# MK66MCU.net
KiCad netlist of a schematic drawn in Altium Designer
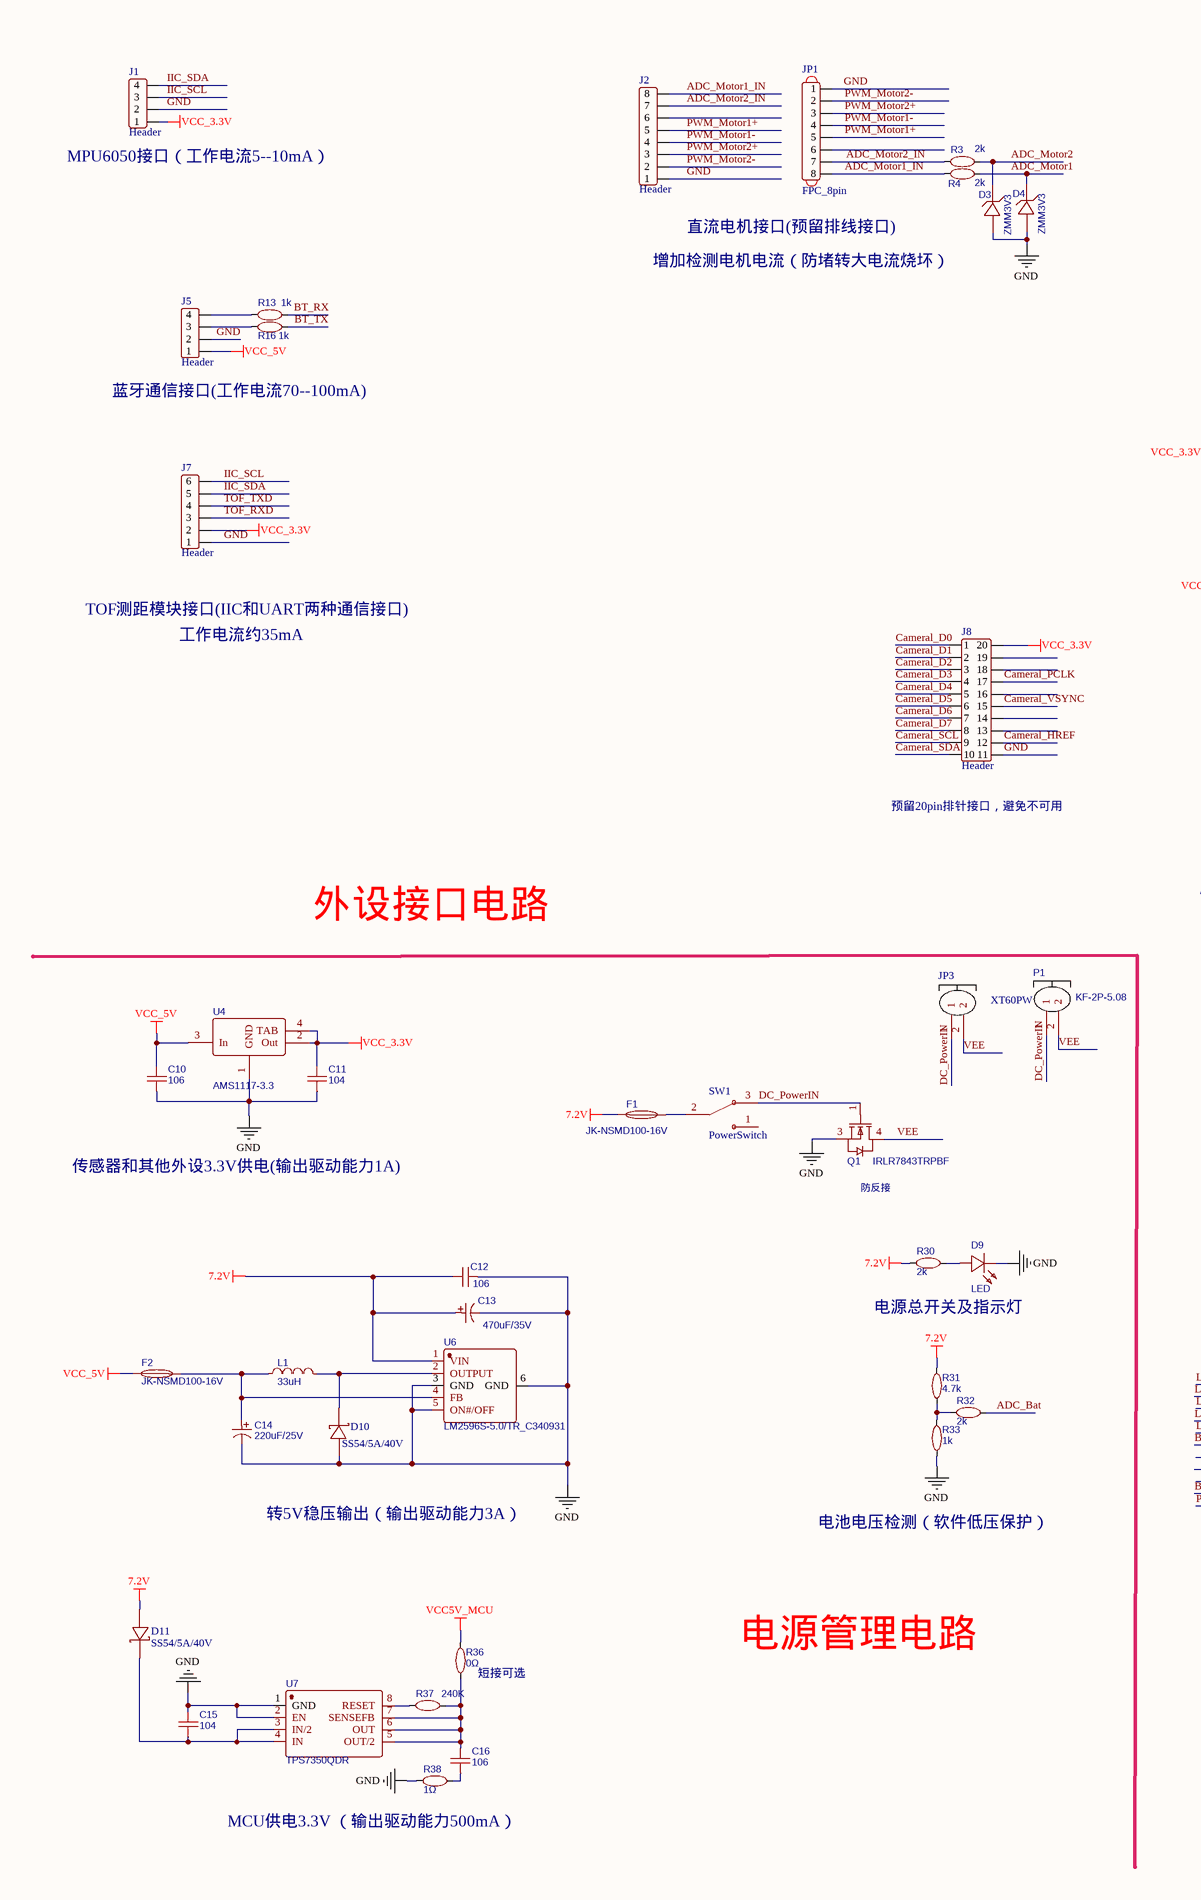
[diagram p0: MK66MCU.SchDoc, left]
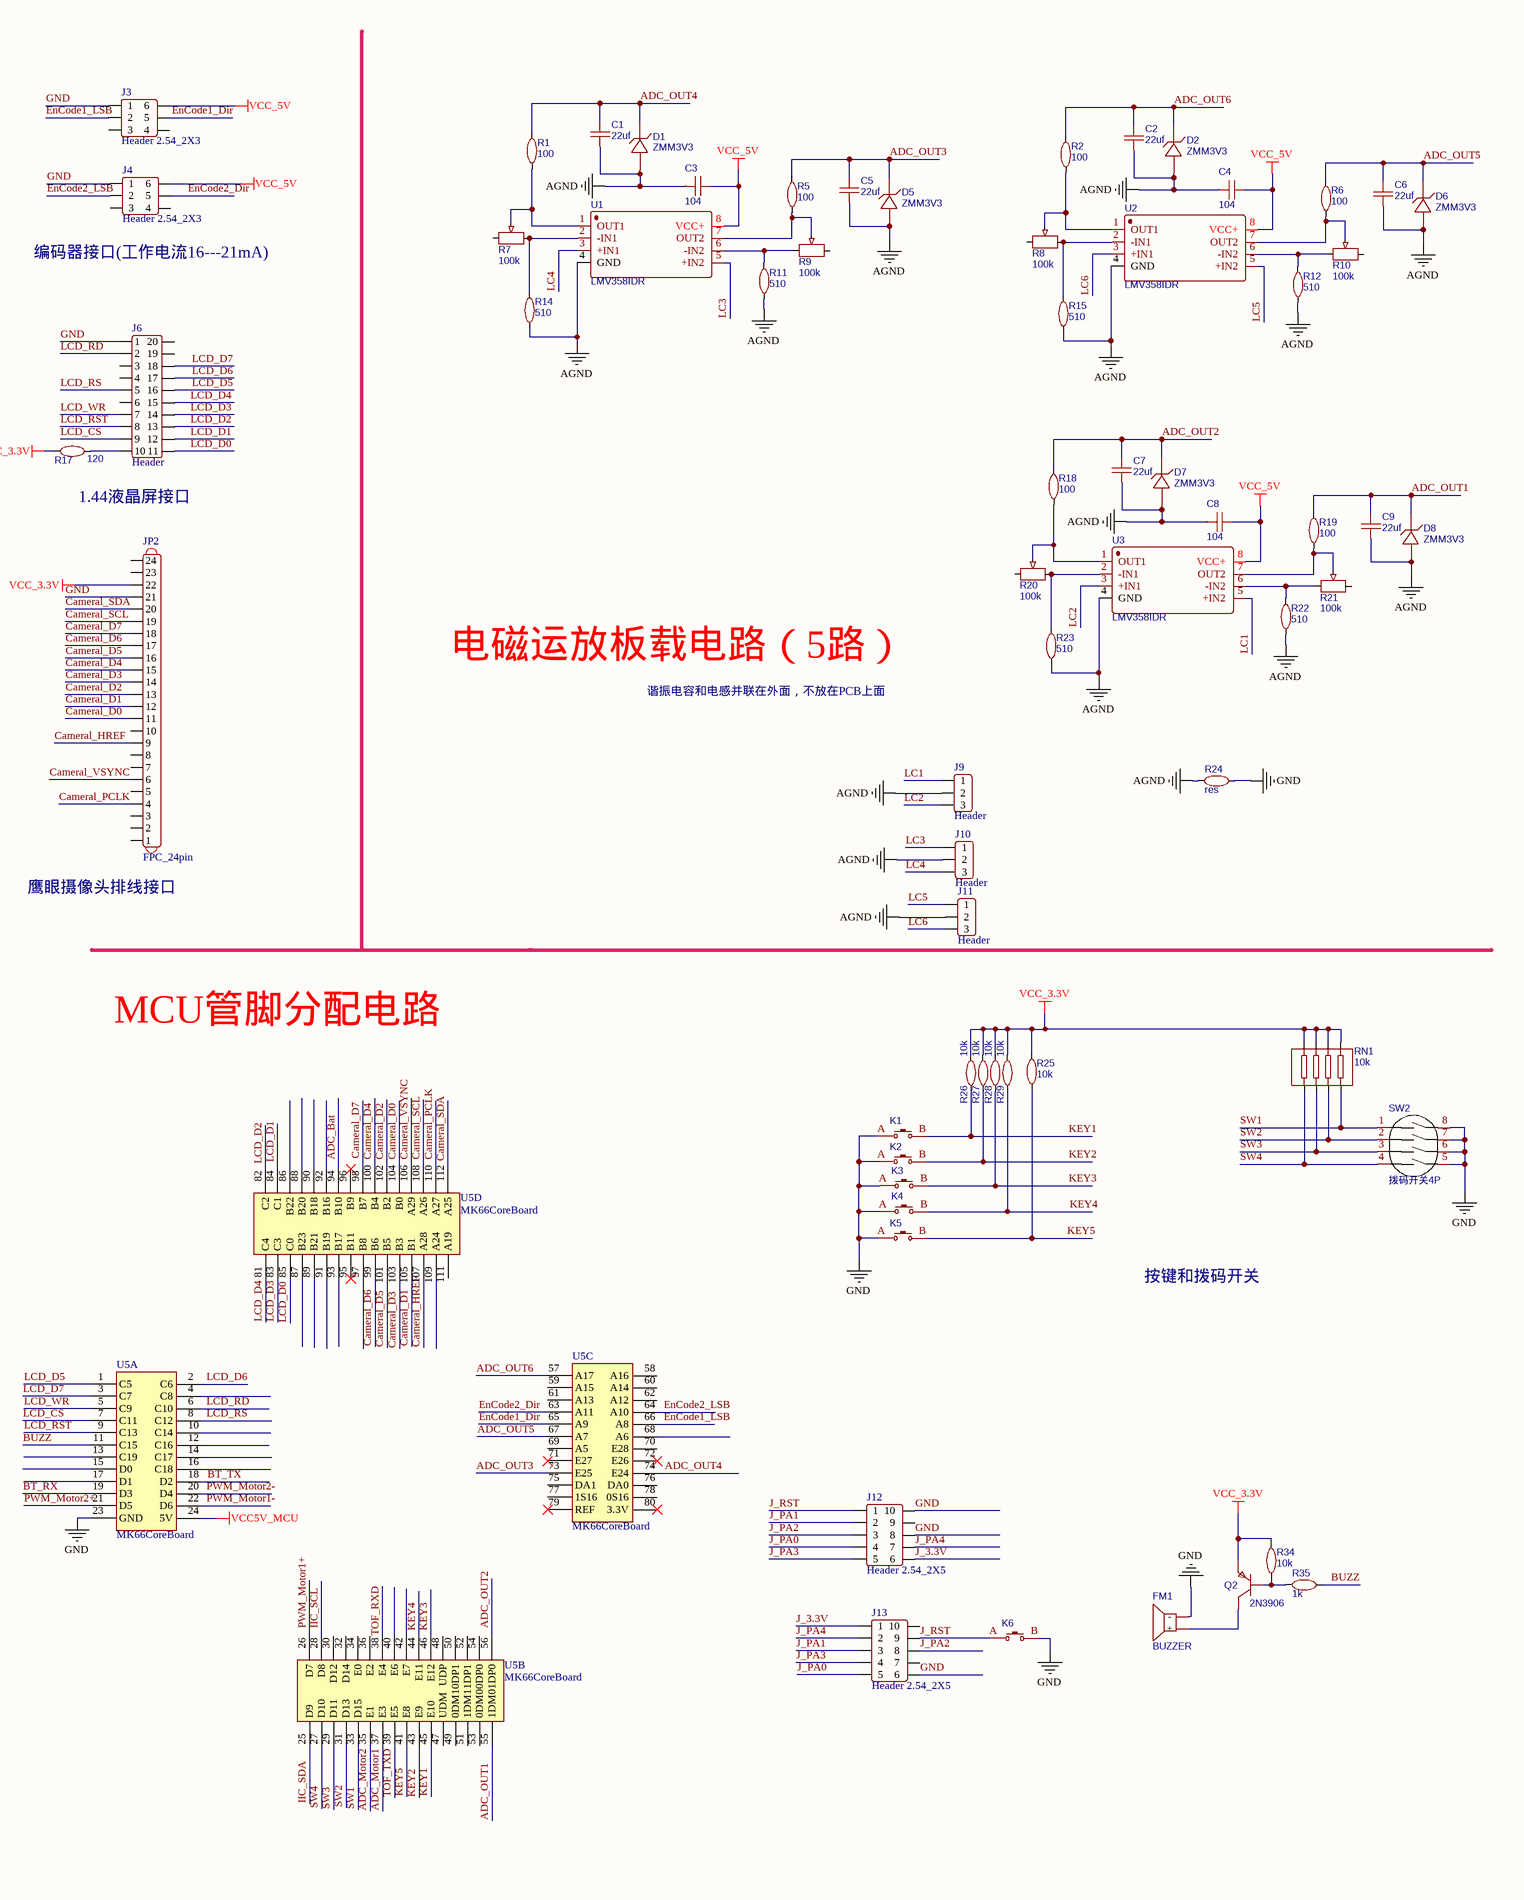
[diagram p1: MK66MCU.SchDoc, right]

(export (version "E")
  (design (tool "Eeschema 10.0.6"))
  (components
    (comp (ref "C1")
      (value "22uf")
      (footprint "CAP_0603")
      (fields
        (field (name "BOM_SUPPLIER PART") "C307348")
        (field (name "BOM_MANUFACTURER PART") "CL10B104KB8WPNC")
        (field (name "CONTRIBUTOR") "LCSC")
      )
      (libsource (lib "LTC_Library1") (part "CAP_0603"))
    )
    (comp (ref "C2")
      (value "22uf")
      (footprint "CAP_0603")
      (fields
        (field (name "BOM_SUPPLIER PART") "C307348")
        (field (name "BOM_MANUFACTURER PART") "CL10B104KB8WPNC")
        (field (name "CONTRIBUTOR") "LCSC")
      )
      (libsource (lib "LTC_Library1") (part "CAP_0603"))
    )
    (comp (ref "C3")
      (value "104")
      (footprint "CAP_0603")
      (fields
        (field (name "BOM_SUPPLIER PART") "C307348")
        (field (name "BOM_MANUFACTURER PART") "CL10B104KB8WPNC")
        (field (name "CONTRIBUTOR") "LCSC")
      )
      (libsource (lib "LTC_Library1") (part "CAP_0603"))
    )
    (comp (ref "C4")
      (value "104")
      (footprint "CAP_0603")
      (fields
        (field (name "BOM_SUPPLIER PART") "C307348")
        (field (name "BOM_MANUFACTURER PART") "CL10B104KB8WPNC")
        (field (name "CONTRIBUTOR") "LCSC")
      )
      (libsource (lib "LTC_Library1") (part "CAP_0603"))
    )
    (comp (ref "C5")
      (value "22uf")
      (footprint "CAP_0603")
      (fields
        (field (name "BOM_SUPPLIER PART") "C307348")
        (field (name "BOM_MANUFACTURER PART") "CL10B104KB8WPNC")
        (field (name "CONTRIBUTOR") "LCSC")
      )
      (libsource (lib "LTC_Library1") (part "CAP_0603"))
    )
    (comp (ref "C6")
      (value "22uf")
      (footprint "CAP_0603")
      (fields
        (field (name "BOM_SUPPLIER PART") "C307348")
        (field (name "BOM_MANUFACTURER PART") "CL10B104KB8WPNC")
        (field (name "CONTRIBUTOR") "LCSC")
      )
      (libsource (lib "LTC_Library1") (part "CAP_0603"))
    )
    (comp (ref "C7")
      (value "22uf")
      (footprint "CAP_0603")
      (fields
        (field (name "BOM_SUPPLIER PART") "C307348")
        (field (name "BOM_MANUFACTURER PART") "CL10B104KB8WPNC")
        (field (name "CONTRIBUTOR") "LCSC")
      )
      (libsource (lib "LTC_Library1") (part "CAP_0603"))
    )
    (comp (ref "C8")
      (value "104")
      (footprint "CAP_0603")
      (fields
        (field (name "BOM_SUPPLIER PART") "C307348")
        (field (name "BOM_MANUFACTURER PART") "CL10B104KB8WPNC")
        (field (name "CONTRIBUTOR") "LCSC")
      )
      (libsource (lib "LTC_Library1") (part "CAP_0603"))
    )
    (comp (ref "C9")
      (value "22uf")
      (footprint "CAP_0603")
      (fields
        (field (name "BOM_SUPPLIER PART") "C307348")
        (field (name "BOM_MANUFACTURER PART") "CL10B104KB8WPNC")
        (field (name "CONTRIBUTOR") "LCSC")
      )
      (libsource (lib "LTC_Library1") (part "CAP_0603"))
    )
    (comp (ref "C10")
      (value "106")
      (footprint "CAP_0603")
      (fields
        (field (name "BOM_SUPPLIER PART") "C307348")
        (field (name "BOM_MANUFACTURER PART") "CL10B104KB8WPNC")
        (field (name "CONTRIBUTOR") "LCSC")
      )
      (libsource (lib "LTC_Library1") (part "CAP_0603"))
    )
    (comp (ref "C11")
      (value "104")
      (footprint "CAP_0603")
      (fields
        (field (name "BOM_SUPPLIER PART") "C307348")
        (field (name "BOM_MANUFACTURER PART") "CL10B104KB8WPNC")
        (field (name "CONTRIBUTOR") "LCSC")
      )
      (libsource (lib "LTC_Library1") (part "CAP_0603"))
    )
    (comp (ref "C12")
      (value "106")
      (footprint "CAP_0603")
      (fields
        (field (name "BOM_SUPPLIER PART") "C307348")
        (field (name "BOM_MANUFACTURER PART") "CL10B104KB8WPNC")
        (field (name "CONTRIBUTOR") "LCSC")
      )
      (libsource (lib "LTC_Library1") (part "CAP_0603"))
    )
    (comp (ref "C13")
      (value "470uF/35V")
      (footprint "CAPE_SMD_F_8.4")
      (description "贴片电解电容")
      (fields
        (field (name "BOM_MANUFACTURER PART") "RVT1C221M0607")
        (field (name "BOM_SUPPLIER PART") "C72496")
      )
      (libsource (lib "LTC_Library1") (part "CAP_E_SMD"))
    )
    (comp (ref "C14")
      (value "220uF/25V")
      (footprint "CAPE_SMD_D_6.4")
      (description "贴片电解电容")
      (fields
        (field (name "BOM_MANUFACTURER PART") "RVT1C221M0607")
        (field (name "BOM_SUPPLIER PART") "C72496")
      )
      (libsource (lib "") (part "CAP_E_SMD_1"))
    )
    (comp (ref "C15")
      (value "104")
      (footprint "CAP_0603")
      (fields
        (field (name "BOM_SUPPLIER PART") "C307348")
        (field (name "BOM_MANUFACTURER PART") "CL10B104KB8WPNC")
        (field (name "CONTRIBUTOR") "LCSC")
      )
      (libsource (lib "LTC_Library1") (part "CAP_0603"))
    )
    (comp (ref "C16")
      (value "106")
      (footprint "CAP_0603")
      (fields
        (field (name "BOM_SUPPLIER PART") "C307348")
        (field (name "BOM_MANUFACTURER PART") "CL10B104KB8WPNC")
        (field (name "CONTRIBUTOR") "LCSC")
      )
      (libsource (lib "LTC_Library1") (part "CAP_0603"))
    )
    (comp (ref "D1")
      (value "ZMM3V3")
      (footprint "LL-34_L3.5-W1.5-RD")
      (fields (field (name "BOM_SUPPLIER PART") "C8056"))
      (libsource (lib "SmartCar_Library") (part "ZMM3V3"))
    )
    (comp (ref "D2")
      (value "ZMM3V3")
      (footprint "LL-34_L3.5-W1.5-RD")
      (fields (field (name "BOM_SUPPLIER PART") "C8056"))
      (libsource (lib "SmartCar_Library") (part "ZMM3V3"))
    )
    (comp (ref "D3")
      (value "ZMM3V3")
      (footprint "LL-34_L3.5-W1.5-RD")
      (fields (field (name "BOM_SUPPLIER PART") "C8056"))
      (libsource (lib "SmartCar_Library") (part "ZMM3V3"))
    )
    (comp (ref "D4")
      (value "ZMM3V3")
      (footprint "LL-34_L3.5-W1.5-RD")
      (fields (field (name "BOM_SUPPLIER PART") "C8056"))
      (libsource (lib "SmartCar_Library") (part "ZMM3V3"))
    )
    (comp (ref "D5")
      (value "ZMM3V3")
      (footprint "LL-34_L3.5-W1.5-RD")
      (fields (field (name "BOM_SUPPLIER PART") "C8056"))
      (libsource (lib "SmartCar_Library") (part "ZMM3V3"))
    )
    (comp (ref "D6")
      (value "ZMM3V3")
      (footprint "LL-34_L3.5-W1.5-RD")
      (fields (field (name "BOM_SUPPLIER PART") "C8056"))
      (libsource (lib "SmartCar_Library") (part "ZMM3V3"))
    )
    (comp (ref "D7")
      (value "ZMM3V3")
      (footprint "LL-34_L3.5-W1.5-RD")
      (fields (field (name "BOM_SUPPLIER PART") "C8056"))
      (libsource (lib "SmartCar_Library") (part "ZMM3V3"))
    )
    (comp (ref "D8")
      (value "ZMM3V3")
      (footprint "LL-34_L3.5-W1.5-RD")
      (fields (field (name "BOM_SUPPLIER PART") "C8056"))
      (libsource (lib "SmartCar_Library") (part "ZMM3V3"))
    )
    (comp (ref "D9")
      (value "LED")
      (footprint "LED_0603_B")
      (description "发光LED")
      (fields
        (field (name "BOM_MANUFACTURER PART") "D-G080508G1")
        (field (name "BOM_SUPPLIER PART") "C107402")
        (field (name "CONTRIBUTOR") "LCSC")
      )
      (libsource (lib "LTC_Library1") (part "LED_0603"))
    )
    (comp (ref "D10")
      (value "SS54/5A/40V")
      (footprint "DO214_SMA")
      (libsource (lib "LTC_Library1") (part "SS54"))
    )
    (comp (ref "D11")
      (value "SS54/5A/40V")
      (footprint "DO214_SMA")
      (libsource (lib "LTC_Library1") (part "SS54"))
    )
    (comp (ref "F1")
      (value "JK-NSMD100-16V")
      (footprint "FUSE_1210")
      (fields (field (name "BOM_SUPPLIER PART") "C369161") (field (name "CONTRIBUTOR") "LCSC"))
      (libsource (lib "SmartCar_Library") (part "JK-NSMD100-16V"))
    )
    (comp (ref "F2")
      (value "JK-NSMD100-16V")
      (footprint "F1206")
      (fields (field (name "BOM_SUPPLIER PART") "C369161") (field (name "CONTRIBUTOR") "LCSC"))
      (libsource (lib "SmartCar_Library") (part "JK-NSMD100-16V"))
    )
    (comp (ref "FM1")
      (value "BUZZER")
      (footprint "BUZZ-12*7.5")
      (description "蜂鸣器")
      (fields (field (name "BOM_MANUFACTURER PART") "TMB12A12") (field (name "BOM_SUPPLIER PART") "C96079"))
      (libsource (lib "LTC_Library1") (part "BUZZER"))
    )
    (comp (ref "J1")
      (value "Header")
      (footprint "Header 2.54X4")
      (libsource (lib "LTC_Library1") (part "Header 2.54_4"))
    )
    (comp (ref "J2")
      (value "Header")
      (footprint "Header 2.54X8")
      (libsource (lib "LTC_Library1") (part "Header 2.54_8"))
    )
    (comp (ref "J3")
      (value "Header 2.54_2X3")
      (footprint "IDC_6P")
      (libsource (lib "LTC_Library1") (part "Header 2.54_2X3"))
    )
    (comp (ref "J4")
      (value "Header 2.54_2X3")
      (footprint "IDC_6P")
      (libsource (lib "LTC_Library1") (part "Header 2.54_2X3"))
    )
    (comp (ref "J5")
      (value "Header")
      (footprint "Header F 2.54X4")
      (libsource (lib "LTC_Library1") (part "Header 2.54_4"))
    )
    (comp (ref "J6")
      (value "Header")
      (footprint "Header F 2.54_2x10")
      (libsource (lib "LTC_Library1") (part "Header 2.54_2X10"))
    )
    (comp (ref "J7")
      (value "Header")
      (footprint "Header 2.54X6")
      (libsource (lib "LTC_Library1") (part "Header 2.54_6"))
    )
    (comp (ref "J8")
      (value "Header")
      (footprint "Header F 2.54_2x10")
      (libsource (lib "LTC_Library1") (part "Header 2.54_2X10"))
    )
    (comp (ref "J9")
      (value "Header")
      (footprint "Header 2.54X3")
      (libsource (lib "LTC_Library1") (part "Header 2.54_3"))
    )
    (comp (ref "J10")
      (value "Header")
      (footprint "Header 2.54X3")
      (libsource (lib "LTC_Library1") (part "Header 2.54_3"))
    )
    (comp (ref "J11")
      (value "Header")
      (footprint "Header 2.54X3")
      (libsource (lib "LTC_Library1") (part "Header 2.54_3"))
    )
    (comp (ref "J12")
      (value "Header 2.54_2X5")
      (footprint "Header 2.54_2X5")
      (libsource (lib "LTC_Library1") (part "Header 2.54_2X5"))
    )
    (comp (ref "J13")
      (value "Header 2.54_2X5")
      (footprint "IDC_10P")
      (libsource (lib "LTC_Library1") (part "Header 2.54_2X5"))
    )
    (comp (ref "JP1")
      (value "FPC_8pin")
      (footprint "FPC_1.0_8P")
      (libsource (lib "LTC_Library1") (part "FPC_8pin"))
    )
    (comp (ref "JP2")
      (value "FPC_24pin")
      (footprint "FPC_0.5_24P")
      (libsource (lib "External Interface") (part "FPC_24pin"))
    )
    (comp (ref "JP3")
      (value "XT60PW")
      (footprint "XT60PW")
      (libsource (lib "SmartCar_Library") (part "XT60PW"))
    )
    (comp (ref "K1")
      (value "TS-Button_2P")
      (footprint "SW_SMD_6.1*3.7")
      (description "贴片按键 3*6*2.5")
      (fields
        (field (name "BOM_SUPPLIER PART") "C455236")
        (field (name "BOM_MANUFACTURER PART") "TS-1007S-26")
        (field (name "CONTRIBUTOR") "LCSC")
      )
      (libsource (lib "LTC_Library1") (part "TS-Button_2P"))
    )
    (comp (ref "K2")
      (value "TS-Button_2P")
      (footprint "SW_SMD_6.1*3.7")
      (description "贴片按键 3*6*2.5")
      (fields
        (field (name "BOM_SUPPLIER PART") "C455236")
        (field (name "BOM_MANUFACTURER PART") "TS-1007S-26")
        (field (name "CONTRIBUTOR") "LCSC")
      )
      (libsource (lib "LTC_Library1") (part "TS-Button_2P"))
    )
    (comp (ref "K3")
      (value "TS-Button_2P")
      (footprint "SW_SMD_6.1*3.7")
      (description "贴片按键 3*6*2.5")
      (fields
        (field (name "BOM_SUPPLIER PART") "C455236")
        (field (name "BOM_MANUFACTURER PART") "TS-1007S-26")
        (field (name "CONTRIBUTOR") "LCSC")
      )
      (libsource (lib "LTC_Library1") (part "TS-Button_2P"))
    )
    (comp (ref "K4")
      (value "TS-Button_2P")
      (footprint "SW_SMD_6.1*3.7")
      (description "贴片按键 3*6*2.5")
      (fields
        (field (name "BOM_SUPPLIER PART") "C455236")
        (field (name "BOM_MANUFACTURER PART") "TS-1007S-26")
        (field (name "CONTRIBUTOR") "LCSC")
      )
      (libsource (lib "LTC_Library1") (part "TS-Button_2P"))
    )
    (comp (ref "K5")
      (value "TS-Button_2P")
      (footprint "SW_SMD_6.1*3.7")
      (description "贴片按键 3*6*2.5")
      (fields
        (field (name "BOM_SUPPLIER PART") "C455236")
        (field (name "BOM_MANUFACTURER PART") "TS-1007S-26")
        (field (name "CONTRIBUTOR") "LCSC")
      )
      (libsource (lib "LTC_Library1") (part "TS-Button_2P"))
    )
    (comp (ref "K6")
      (value "TS-Button_2P")
      (footprint "SW_SMD_6.1*3.7")
      (description "贴片按键 3*6*2.5")
      (fields
        (field (name "BOM_SUPPLIER PART") "C455236")
        (field (name "BOM_MANUFACTURER PART") "TS-1007S-26")
        (field (name "CONTRIBUTOR") "LCSC")
      )
      (libsource (lib "LTC_Library1") (part "TS-Button_2P"))
    )
    (comp (ref "L1")
      (value "33uH")
      (footprint "IND-SMD_L8.0-W8.0")
      (fields
        (field (name "BOM_SUPPLIER PART") "C295130")
        (field (name "BOM_MANUFACTURER PART") "NLV25T-330J-EF")
        (field (name "CONTRIBUTOR") "LCSC")
      )
      (libsource (lib "SmartCar_Library") (part "Inductor"))
    )
    (comp (ref "P1")
      (value "KF-2P-5.08")
      (footprint "KF_2P-5.08")
      (description "端子2P")
      (fields
        (field (name "BOM_MANUFACTURER PART") "WJ500H-5.08-2P")
        (field (name "BOM_SUPPLIER PART") "C8478")
      )
      (libsource (lib "LTC_Library1") (part "KF-2P-5.08"))
    )
    (comp (ref "Q1")
      (value "IRLR7843TRPBF")
      (footprint "TO-252-2")
      (description "MOS管")
      (fields (field (name "BOM_SUPPLIER PART") "C21988"))
      (libsource (lib "LTC_Library1") (part "IRLR7843TRPBF"))
    )
    (comp (ref "Q2")
      (value "2N3906")
      (footprint "TO_92A")
      (description "三极管PNP")
      (fields (field (name "BOM_SUPPLIER PART") "C305396") (field (name "CONTRIBUTOR") "LCSC"))
      (libsource (lib "LTC_Library1") (part "2N3906"))
    )
    (comp (ref "R1")
      (value "100")
      (footprint "RES_0603")
      (fields
        (field (name "BOM_MANUFACTURER PART") "RC0402JR-07100KL")
        (field (name "BOM_SUPPLIER PART") "C106234")
      )
      (libsource (lib "LTC_Library1") (part "RES_0603"))
    )
    (comp (ref "R2")
      (value "100")
      (footprint "RES_0603")
      (fields
        (field (name "BOM_MANUFACTURER PART") "RC0402JR-07100KL")
        (field (name "BOM_SUPPLIER PART") "C106234")
      )
      (libsource (lib "LTC_Library1") (part "RES_0603"))
    )
    (comp (ref "R3")
      (value "2k")
      (footprint "RES_0603")
      (fields
        (field (name "BOM_MANUFACTURER PART") "RC0402JR-07100KL")
        (field (name "BOM_SUPPLIER PART") "C106234")
      )
      (libsource (lib "LTC_Library1") (part "RES_0603"))
    )
    (comp (ref "R4")
      (value "2k")
      (footprint "RES_0603")
      (fields
        (field (name "BOM_MANUFACTURER PART") "RC0402JR-07100KL")
        (field (name "BOM_SUPPLIER PART") "C106234")
      )
      (libsource (lib "LTC_Library1") (part "RES_0603"))
    )
    (comp (ref "R5")
      (value "100")
      (footprint "RES_0603")
      (fields
        (field (name "BOM_MANUFACTURER PART") "RC0402JR-07100KL")
        (field (name "BOM_SUPPLIER PART") "C106234")
      )
      (libsource (lib "LTC_Library1") (part "RES_0603"))
    )
    (comp (ref "R6")
      (value "100")
      (footprint "RES_0603")
      (fields
        (field (name "BOM_MANUFACTURER PART") "RC0402JR-07100KL")
        (field (name "BOM_SUPPLIER PART") "C106234")
      )
      (libsource (lib "LTC_Library1") (part "RES_0603"))
    )
    (comp (ref "R7")
      (value "100k")
      (footprint "RES_POT-3296W")
      (description "可调电阻3296W")
      (fields
        (field (name "BOM_SUPPLIER PART") "C118963")
        (field (name "BOM_MANUFACTURER PART") "3296W-1-104")
        (field (name "CONTRIBUTOR") "LCSC")
      )
      (libsource (lib "LTC_Library1") (part "RES_POT-3296W"))
    )
    (comp (ref "R8")
      (value "100k")
      (footprint "RES_POT-3296W")
      (description "可调电阻3296W")
      (fields
        (field (name "BOM_SUPPLIER PART") "C118963")
        (field (name "BOM_MANUFACTURER PART") "3296W-1-104")
        (field (name "CONTRIBUTOR") "LCSC")
      )
      (libsource (lib "LTC_Library1") (part "RES_POT-3296W"))
    )
    (comp (ref "R9")
      (value "100k")
      (footprint "RES_POT-3296W")
      (description "可调电阻3296W")
      (fields
        (field (name "BOM_SUPPLIER PART") "C118963")
        (field (name "BOM_MANUFACTURER PART") "3296W-1-104")
        (field (name "CONTRIBUTOR") "LCSC")
      )
      (libsource (lib "LTC_Library1") (part "RES_POT-3296W"))
    )
    (comp (ref "R10")
      (value "100k")
      (footprint "RES_POT-3296W")
      (description "可调电阻3296W")
      (fields
        (field (name "BOM_SUPPLIER PART") "C118963")
        (field (name "BOM_MANUFACTURER PART") "3296W-1-104")
        (field (name "CONTRIBUTOR") "LCSC")
      )
      (libsource (lib "LTC_Library1") (part "RES_POT-3296W"))
    )
    (comp (ref "R11")
      (value "510")
      (footprint "RES_0603")
      (fields
        (field (name "BOM_MANUFACTURER PART") "RC0402JR-07100KL")
        (field (name "BOM_SUPPLIER PART") "C106234")
      )
      (libsource (lib "LTC_Library1") (part "RES_0603"))
    )
    (comp (ref "R12")
      (value "510")
      (footprint "RES_0603")
      (fields
        (field (name "BOM_MANUFACTURER PART") "RC0402JR-07100KL")
        (field (name "BOM_SUPPLIER PART") "C106234")
      )
      (libsource (lib "LTC_Library1") (part "RES_0603"))
    )
    (comp (ref "R13")
      (value "1k")
      (footprint "RES_0603")
      (fields
        (field (name "BOM_MANUFACTURER PART") "RC0402JR-07100KL")
        (field (name "BOM_SUPPLIER PART") "C106234")
      )
      (libsource (lib "LTC_Library1") (part "RES_0603"))
    )
    (comp (ref "R14")
      (value "510")
      (footprint "RES_0603")
      (fields
        (field (name "BOM_MANUFACTURER PART") "RC0402JR-07100KL")
        (field (name "BOM_SUPPLIER PART") "C106234")
      )
      (libsource (lib "LTC_Library1") (part "RES_0603"))
    )
    (comp (ref "R15")
      (value "510")
      (footprint "RES_0603")
      (fields
        (field (name "BOM_MANUFACTURER PART") "RC0402JR-07100KL")
        (field (name "BOM_SUPPLIER PART") "C106234")
      )
      (libsource (lib "LTC_Library1") (part "RES_0603"))
    )
    (comp (ref "R16")
      (value "1k")
      (footprint "RES_0603")
      (fields
        (field (name "BOM_MANUFACTURER PART") "RC0402JR-07100KL")
        (field (name "BOM_SUPPLIER PART") "C106234")
      )
      (libsource (lib "LTC_Library1") (part "RES_0603"))
    )
    (comp (ref "R17")
      (value "120")
      (footprint "RES_0603")
      (fields
        (field (name "BOM_MANUFACTURER PART") "RC0402JR-07100KL")
        (field (name "BOM_SUPPLIER PART") "C106234")
      )
      (libsource (lib "LTC_Library1") (part "RES_0603"))
    )
    (comp (ref "R18")
      (value "100")
      (footprint "RES_0603")
      (fields
        (field (name "BOM_MANUFACTURER PART") "RC0402JR-07100KL")
        (field (name "BOM_SUPPLIER PART") "C106234")
      )
      (libsource (lib "LTC_Library1") (part "RES_0603"))
    )
    (comp (ref "R19")
      (value "100")
      (footprint "RES_0603")
      (fields
        (field (name "BOM_MANUFACTURER PART") "RC0402JR-07100KL")
        (field (name "BOM_SUPPLIER PART") "C106234")
      )
      (libsource (lib "LTC_Library1") (part "RES_0603"))
    )
    (comp (ref "R20")
      (value "100k")
      (footprint "RES_POT-3296W")
      (description "可调电阻3296W")
      (fields
        (field (name "BOM_SUPPLIER PART") "C118963")
        (field (name "BOM_MANUFACTURER PART") "3296W-1-104")
        (field (name "CONTRIBUTOR") "LCSC")
      )
      (libsource (lib "LTC_Library1") (part "RES_POT-3296W"))
    )
    (comp (ref "R21")
      (value "100k")
      (footprint "RES_POT-3296W")
      (description "可调电阻3296W")
      (fields
        (field (name "BOM_SUPPLIER PART") "C118963")
        (field (name "BOM_MANUFACTURER PART") "3296W-1-104")
        (field (name "CONTRIBUTOR") "LCSC")
      )
      (libsource (lib "LTC_Library1") (part "RES_POT-3296W"))
    )
    (comp (ref "R22")
      (value "510")
      (footprint "RES_0603")
      (fields
        (field (name "BOM_MANUFACTURER PART") "RC0402JR-07100KL")
        (field (name "BOM_SUPPLIER PART") "C106234")
      )
      (libsource (lib "LTC_Library1") (part "RES_0603"))
    )
    (comp (ref "R23")
      (value "510")
      (footprint "RES_0603")
      (fields
        (field (name "BOM_MANUFACTURER PART") "RC0402JR-07100KL")
        (field (name "BOM_SUPPLIER PART") "C106234")
      )
      (libsource (lib "LTC_Library1") (part "RES_0603"))
    )
    (comp (ref "R24")
      (value "res")
      (footprint "RES_0805")
      (fields
        (field (name "BOM_MANUFACTURER PART") "RC0402JR-07100KL")
        (field (name "BOM_SUPPLIER PART") "C106234")
      )
      (libsource (lib "LTC_Library1") (part "RES_0805"))
    )
    (comp (ref "R25")
      (value "10k")
      (footprint "RES_0603")
      (fields
        (field (name "BOM_MANUFACTURER PART") "RC0402JR-07100KL")
        (field (name "BOM_SUPPLIER PART") "C106234")
      )
      (libsource (lib "LTC_Library1") (part "RES_0603"))
    )
    (comp (ref "R26")
      (value "10k")
      (footprint "RES_0603")
      (fields
        (field (name "BOM_MANUFACTURER PART") "RC0402JR-07100KL")
        (field (name "BOM_SUPPLIER PART") "C106234")
      )
      (libsource (lib "LTC_Library1") (part "RES_0603"))
    )
    (comp (ref "R27")
      (value "10k")
      (footprint "RES_0603")
      (fields
        (field (name "BOM_MANUFACTURER PART") "RC0402JR-07100KL")
        (field (name "BOM_SUPPLIER PART") "C106234")
      )
      (libsource (lib "LTC_Library1") (part "RES_0603"))
    )
    (comp (ref "R28")
      (value "10k")
      (footprint "RES_0603")
      (fields
        (field (name "BOM_MANUFACTURER PART") "RC0402JR-07100KL")
        (field (name "BOM_SUPPLIER PART") "C106234")
      )
      (libsource (lib "LTC_Library1") (part "RES_0603"))
    )
    (comp (ref "R29")
      (value "10k")
      (footprint "RES_0603")
      (fields
        (field (name "BOM_MANUFACTURER PART") "RC0402JR-07100KL")
        (field (name "BOM_SUPPLIER PART") "C106234")
      )
      (libsource (lib "LTC_Library1") (part "RES_0603"))
    )
    (comp (ref "R30")
      (value "2k")
      (footprint "RES_0603")
      (fields
        (field (name "BOM_MANUFACTURER PART") "RC0402JR-07100KL")
        (field (name "BOM_SUPPLIER PART") "C106234")
      )
      (libsource (lib "LTC_Library1") (part "RES_0603"))
    )
    (comp (ref "R31")
      (value "4.7k")
      (footprint "RES_0603")
      (fields
        (field (name "BOM_MANUFACTURER PART") "RC0402JR-07100KL")
        (field (name "BOM_SUPPLIER PART") "C106234")
      )
      (libsource (lib "LTC_Library1") (part "RES_0603"))
    )
    (comp (ref "R32")
      (value "2k")
      (footprint "RES_0603")
      (fields
        (field (name "BOM_MANUFACTURER PART") "RC0402JR-07100KL")
        (field (name "BOM_SUPPLIER PART") "C106234")
      )
      (libsource (lib "LTC_Library1") (part "RES_0603"))
    )
    (comp (ref "R33")
      (value "1k")
      (footprint "RES_0603")
      (fields
        (field (name "BOM_MANUFACTURER PART") "RC0402JR-07100KL")
        (field (name "BOM_SUPPLIER PART") "C106234")
      )
      (libsource (lib "LTC_Library1") (part "RES_0603"))
    )
    (comp (ref "R34")
      (value "10k")
      (footprint "RES_0603")
      (fields
        (field (name "BOM_MANUFACTURER PART") "RC0402JR-07100KL")
        (field (name "BOM_SUPPLIER PART") "C106234")
      )
      (libsource (lib "LTC_Library1") (part "RES_0603"))
    )
    (comp (ref "R35")
      (value "1k")
      (footprint "RES_0603")
      (fields
        (field (name "BOM_MANUFACTURER PART") "RC0402JR-07100KL")
        (field (name "BOM_SUPPLIER PART") "C106234")
      )
      (libsource (lib "LTC_Library1") (part "RES_0603"))
    )
    (comp (ref "R36")
      (value "0Ω")
      (footprint "RES_0603")
      (fields
        (field (name "BOM_MANUFACTURER PART") "RC0402JR-07100KL")
        (field (name "BOM_SUPPLIER PART") "C106234")
      )
      (libsource (lib "LTC_Library1") (part "RES_0603"))
    )
    (comp (ref "R37")
      (value "240K")
      (footprint "RES_0603")
      (fields
        (field (name "BOM_MANUFACTURER PART") "RC0402JR-07100KL")
        (field (name "BOM_SUPPLIER PART") "C106234")
      )
      (libsource (lib "LTC_Library1") (part "RES_0603"))
    )
    (comp (ref "R38")
      (value "1Ω")
      (footprint "RES_0603")
      (fields
        (field (name "BOM_MANUFACTURER PART") "RC0402JR-07100KL")
        (field (name "BOM_SUPPLIER PART") "C106234")
      )
      (libsource (lib "LTC_Library1") (part "RES_0603"))
    )
    (comp (ref "RN1")
      (value "10k")
      (footprint "RES-ARRAY-SMD_0603-8P-L3.2-W1.6-BL")
      (fields
        (field (name "BOM_MANUFACTURER PART") "YC164-JR-0710KL")
        (field (name "BOM_SUPPLIER PART") "C107374")
      )
      (libsource (lib "SmartCar_Library") (part "RESW4"))
    )
    (comp (ref "SW1")
      (value "PowerSwitch")
      (footprint "SW-TH_K3-1260D-K1")
      (libsource (lib "SmartCar_Library") (part "PowerSwitch"))
    )
    (comp (ref "SW2")
      (value "拨码开关4P")
      (footprint "VDG/S-04HG-R")
      (description "DIP_4PX2*2.54")
      (fields
        (field (name "BOM_MANUFACTURER PART") "VDG/S-04HG-R")
        (field (name "BOM_SUPPLIER PART") "C15781")
      )
      (libsource (lib "LTC_Library1") (part "拨码开关4P"))
    )
    (comp (ref "U1")
      (value "LMV358IDR")
      (footprint "SOIC-8_150MIL")
      (fields (field (name "BOM_SUPPLIER PART") "C63813"))
      (libsource (lib "LTC_Library1") (part "LMV358IDR"))
    )
    (comp (ref "U2")
      (value "LMV358IDR")
      (footprint "SOIC-8_150MIL")
      (fields (field (name "BOM_SUPPLIER PART") "C63813"))
      (libsource (lib "LTC_Library1") (part "LMV358IDR"))
    )
    (comp (ref "U3")
      (value "LMV358IDR")
      (footprint "SOIC-8_150MIL")
      (fields (field (name "BOM_SUPPLIER PART") "C63813"))
      (libsource (lib "LTC_Library1") (part "LMV358IDR"))
    )
    (comp (ref "U4")
      (value "AMS1117-3.3")
      (footprint "SOT-223_3")
      (fields (field (name "BOM_SUPPLIER PART") "C165482") (field (name "CONTRIBUTOR") "LCSC"))
      (libsource (lib "LTC_Library1") (part "AMS1117-3.3"))
    )
    (comp (ref "U5")
      (value "MK66CoreBoard")
      (footprint "MK66_MCU")
      (libsource (lib "") (part "MK66CoreBoard_1"))
    )
    (comp (ref "U6")
      (value "LM2596S-5.0/TR_C340931")
      (footprint "TO-263_5")
      (fields
        (field (name "BOM_SUPPLIER PART") "C340931")
        (field (name "BOM_MANUFACTURER PART") "LM2596S-5.0/TR")
        (field (name "CONTRIBUTOR") "LCSC")
      )
      (libsource (lib "LTC_Library1") (part "LM2596S-5.0/TR_C340931"))
    )
    (comp (ref "U7")
      (value "TPS7350QDR")
      (footprint "SOIC-8_150MIL")
      (fields (field (name "BOM_MANUFACTURER PART") "TPS7333QDR") (field (name "BOM_SUPPLIER PART") "C23791"))
      (libsource (lib "LTC_Library1") (part "TPS7350QDR"))
    )
  )
  (nets
    (net (code "1") (name "/ADC_Bat") (class "Default")
      (node (ref "R32") (pin "2") (pinfunction "2_2") (pintype "passive"))
      (node (ref "U5") (pin "94") (pinfunction "B10_94") (pintype "passive"))
    )
    (net (code "2") (name "/ADC_Motor1") (class "Default")
      (node (ref "D4") (pin "1") (pinfunction "C_1") (pintype "passive"))
      (node (ref "R4") (pin "1") (pinfunction "1_1") (pintype "passive"))
      (node (ref "U5") (pin "37") (pinfunction "E3_37") (pintype "passive"))
    )
    (net (code "3") (name "/ADC_Motor1_IN") (class "Default")
      (node (ref "J2") (pin "8") (pinfunction "8_8") (pintype "passive"))
      (node (ref "JP1") (pin "8") (pinfunction "8_8") (pintype "passive"))
      (node (ref "R4") (pin "2") (pinfunction "2_2") (pintype "passive"))
    )
    (net (code "4") (name "/ADC_Motor2") (class "Default")
      (node (ref "D3") (pin "1") (pinfunction "C_1") (pintype "passive"))
      (node (ref "R3") (pin "1") (pinfunction "1_1") (pintype "passive"))
      (node (ref "U5") (pin "35") (pinfunction "E1_35") (pintype "passive"))
    )
    (net (code "5") (name "/ADC_Motor2_IN") (class "Default")
      (node (ref "J2") (pin "7") (pinfunction "7_7") (pintype "passive"))
      (node (ref "JP1") (pin "7") (pinfunction "7_7") (pintype "passive"))
      (node (ref "R3") (pin "2") (pinfunction "2_2") (pintype "passive"))
    )
    (net (code "6") (name "/ADC_OUT1") (class "Default")
      (node (ref "C9") (pin "1") (pinfunction "1_1") (pintype "passive"))
      (node (ref "D8") (pin "1") (pinfunction "C_1") (pintype "passive"))
      (node (ref "R19") (pin "1") (pinfunction "1_1") (pintype "passive"))
      (node (ref "U5") (pin "55") (pinfunction "1DM0_55") (pintype "passive"))
    )
    (net (code "7") (name "/ADC_OUT2") (class "Default")
      (node (ref "C7") (pin "1") (pinfunction "1_1") (pintype "passive"))
      (node (ref "D7") (pin "1") (pinfunction "C_1") (pintype "passive"))
      (node (ref "R18") (pin "1") (pinfunction "1_1") (pintype "passive"))
      (node (ref "U5") (pin "56") (pinfunction "1DP0_56") (pintype "passive"))
    )
    (net (code "8") (name "/ADC_OUT3") (class "Default")
      (node (ref "C5") (pin "1") (pinfunction "1_1") (pintype "passive"))
      (node (ref "D5") (pin "1") (pinfunction "C_1") (pintype "passive"))
      (node (ref "R5") (pin "1") (pinfunction "1_1") (pintype "passive"))
      (node (ref "U5") (pin "73") (pinfunction "E25_73") (pintype "passive"))
    )
    (net (code "9") (name "/ADC_OUT4") (class "Default")
      (node (ref "C1") (pin "1") (pinfunction "1_1") (pintype "passive"))
      (node (ref "D1") (pin "1") (pinfunction "C_1") (pintype "passive"))
      (node (ref "R1") (pin "1") (pinfunction "1_1") (pintype "passive"))
      (node (ref "U5") (pin "74") (pinfunction "E24_74") (pintype "passive"))
    )
    (net (code "10") (name "/ADC_OUT5") (class "Default")
      (node (ref "C6") (pin "1") (pinfunction "1_1") (pintype "passive"))
      (node (ref "D6") (pin "1") (pinfunction "C_1") (pintype "passive"))
      (node (ref "R6") (pin "1") (pinfunction "1_1") (pintype "passive"))
      (node (ref "U5") (pin "67") (pinfunction "A7_67") (pintype "passive"))
    )
    (net (code "11") (name "/ADC_OUT6") (class "Default")
      (node (ref "C2") (pin "1") (pinfunction "1_1") (pintype "passive"))
      (node (ref "D2") (pin "1") (pinfunction "C_1") (pintype "passive"))
      (node (ref "R2") (pin "1") (pinfunction "1_1") (pintype "passive"))
      (node (ref "U5") (pin "57") (pinfunction "A17_57") (pintype "passive"))
    )
    (net (code "12") (name "/BT_RX") (class "Default")
      (node (ref "R13") (pin "1") (pinfunction "1_1") (pintype "passive"))
      (node (ref "U5") (pin "19") (pinfunction "D3_19") (pintype "passive"))
    )
    (net (code "13") (name "/BT_TX") (class "Default")
      (node (ref "R16") (pin "1") (pinfunction "1_1") (pintype "passive"))
      (node (ref "U5") (pin "18") (pinfunction "D2_18") (pintype "passive"))
    )
    (net (code "14") (name "/BUZZ") (class "Default")
      (node (ref "R35") (pin "1") (pinfunction "1_1") (pintype "passive"))
      (node (ref "U5") (pin "11") (pinfunction "C15_11") (pintype "passive"))
    )
    (net (code "15") (name "/Cameral_D0") (class "Default")
      (node (ref "J8") (pin "1") (pinfunction "1_1") (pintype "passive"))
      (node (ref "JP2") (pin "11") (pinfunction "11_11") (pintype "passive"))
      (node (ref "U5") (pin "104") (pinfunction "B0_104") (pintype "passive"))
    )
    (net (code "16") (name "/Cameral_D1") (class "Default")
      (node (ref "J8") (pin "2") (pinfunction "2_2") (pintype "passive"))
      (node (ref "JP2") (pin "12") (pinfunction "12_12") (pintype "passive"))
      (node (ref "U5") (pin "105") (pinfunction "B1_105") (pintype "passive"))
    )
    (net (code "17") (name "/Cameral_D2") (class "Default")
      (node (ref "J8") (pin "3") (pinfunction "3_3") (pintype "passive"))
      (node (ref "JP2") (pin "13") (pinfunction "13_13") (pintype "passive"))
      (node (ref "U5") (pin "102") (pinfunction "B2_102") (pintype "passive"))
    )
    (net (code "18") (name "/Cameral_D3") (class "Default")
      (node (ref "J8") (pin "4") (pinfunction "4_4") (pintype "passive"))
      (node (ref "JP2") (pin "14") (pinfunction "14_14") (pintype "passive"))
      (node (ref "U5") (pin "103") (pinfunction "B3_103") (pintype "passive"))
    )
    (net (code "19") (name "/Cameral_D4") (class "Default")
      (node (ref "J8") (pin "5") (pinfunction "5_5") (pintype "passive"))
      (node (ref "JP2") (pin "15") (pinfunction "15_15") (pintype "passive"))
      (node (ref "U5") (pin "100") (pinfunction "B4_100") (pintype "passive"))
    )
    (net (code "20") (name "/Cameral_D5") (class "Default")
      (node (ref "J8") (pin "6") (pinfunction "6_6") (pintype "passive"))
      (node (ref "JP2") (pin "16") (pinfunction "16_16") (pintype "passive"))
      (node (ref "U5") (pin "101") (pinfunction "B5_101") (pintype "passive"))
    )
    (net (code "21") (name "/Cameral_D6") (class "Default")
      (node (ref "J8") (pin "7") (pinfunction "7_7") (pintype "passive"))
      (node (ref "JP2") (pin "17") (pinfunction "17_17") (pintype "passive"))
      (node (ref "U5") (pin "99") (pinfunction "B6_99") (pintype "passive"))
    )
    (net (code "22") (name "/Cameral_D7") (class "Default")
      (node (ref "J8") (pin "8") (pinfunction "8_8") (pintype "passive"))
      (node (ref "JP2") (pin "18") (pinfunction "18_18") (pintype "passive"))
      (node (ref "U5") (pin "98") (pinfunction "B7_98") (pintype "passive"))
    )
    (net (code "23") (name "/Cameral_HREF") (class "Default")
      (node (ref "J8") (pin "12") (pinfunction "12_12") (pintype "passive"))
      (node (ref "JP2") (pin "9") (pinfunction "9_9") (pintype "passive"))
      (node (ref "U5") (pin "107") (pinfunction "A28_107") (pintype "passive"))
    )
    (net (code "24") (name "/Cameral_PCLK") (class "Default")
      (node (ref "J8") (pin "17") (pinfunction "17_17") (pintype "passive"))
      (node (ref "JP2") (pin "4") (pinfunction "4_4") (pintype "passive"))
      (node (ref "U5") (pin "110") (pinfunction "A27_110") (pintype "passive"))
    )
    (net (code "25") (name "/Cameral_SCL") (class "Default")
      (node (ref "J8") (pin "9") (pinfunction "9_9") (pintype "passive"))
      (node (ref "JP2") (pin "19") (pinfunction "19_19") (pintype "passive"))
      (node (ref "U5") (pin "108") (pinfunction "A26_108") (pintype "passive"))
    )
    (net (code "26") (name "/Cameral_SDA") (class "Default")
      (node (ref "J8") (pin "10") (pinfunction "10_10") (pintype "passive"))
      (node (ref "JP2") (pin "20") (pinfunction "20_20") (pintype "passive"))
      (node (ref "U5") (pin "112") (pinfunction "A25_112") (pintype "passive"))
    )
    (net (code "27") (name "/Cameral_VSYNC") (class "Default")
      (node (ref "J8") (pin "15") (pinfunction "15_15") (pintype "passive"))
      (node (ref "JP2") (pin "6") (pinfunction "6_6") (pintype "passive"))
      (node (ref "U5") (pin "106") (pinfunction "A29_106") (pintype "passive"))
    )
    (net (code "28") (name "/DC_PowerIN") (class "Default")
      (node (ref "JP3") (pin "1") (pinfunction "1_1") (pintype "passive"))
      (node (ref "P1") (pin "1") (pinfunction "1_1") (pintype "passive"))
      (node (ref "Q1") (pin "1") (pinfunction "G_1") (pintype "passive"))
      (node (ref "SW1") (pin "3") (pinfunction "NC_3") (pintype "passive"))
    )
    (net (code "29") (name "/EnCode1_Dir") (class "Default")
      (node (ref "J3") (pin "5") (pinfunction "5_5") (pintype "passive"))
      (node (ref "U5") (pin "65") (pinfunction "A9_65") (pintype "passive"))
    )
    (net (code "30") (name "/EnCode1_LSB") (class "Default")
      (node (ref "J3") (pin "2") (pinfunction "2_2") (pintype "passive"))
      (node (ref "U5") (pin "66") (pinfunction "A8_66") (pintype "passive"))
    )
    (net (code "31") (name "/EnCode2_Dir") (class "Default")
      (node (ref "J4") (pin "5") (pinfunction "5_5") (pintype "passive"))
      (node (ref "U5") (pin "63") (pinfunction "A11_63") (pintype "passive"))
    )
    (net (code "32") (name "/EnCode2_LSB") (class "Default")
      (node (ref "J4") (pin "2") (pinfunction "2_2") (pintype "passive"))
      (node (ref "U5") (pin "64") (pinfunction "A10_64") (pintype "passive"))
    )
    (net (code "33") (name "/IIC_SCL") (class "Default")
      (node (ref "J1") (pin "3") (pinfunction "3_3") (pintype "passive"))
      (node (ref "J7") (pin "6") (pinfunction "6_6") (pintype "passive"))
      (node (ref "U5") (pin "28") (pinfunction "D8_28") (pintype "passive"))
    )
    (net (code "34") (name "/IIC_SDA") (class "Default")
      (node (ref "J1") (pin "4") (pinfunction "4_4") (pintype "passive"))
      (node (ref "J7") (pin "5") (pinfunction "5_5") (pintype "passive"))
      (node (ref "U5") (pin "25") (pinfunction "D9_25") (pintype "passive"))
    )
    (net (code "35") (name "/J_3.3V") (class "Default")
      (node (ref "J12") (pin "6") (pinfunction "6_6") (pintype "passive"))
      (node (ref "J13") (pin "1") (pinfunction "1_1") (pintype "passive"))
    )
    (net (code "36") (name "/J_PA0") (class "Default")
      (node (ref "J12") (pin "4") (pinfunction "4_4") (pintype "passive"))
      (node (ref "J13") (pin "5") (pinfunction "5_5") (pintype "passive"))
    )
    (net (code "37") (name "/J_PA1") (class "Default")
      (node (ref "J12") (pin "2") (pinfunction "2_2") (pintype "passive"))
      (node (ref "J13") (pin "3") (pinfunction "3_3") (pintype "passive"))
    )
    (net (code "38") (name "/J_PA2") (class "Default")
      (node (ref "J12") (pin "3") (pinfunction "3_3") (pintype "passive"))
      (node (ref "J13") (pin "8") (pinfunction "8_8") (pintype "passive"))
    )
    (net (code "39") (name "/J_PA3") (class "Default")
      (node (ref "J12") (pin "5") (pinfunction "5_5") (pintype "passive"))
      (node (ref "J13") (pin "4") (pinfunction "4_4") (pintype "passive"))
    )
    (net (code "40") (name "/J_PA4") (class "Default")
      (node (ref "J12") (pin "7") (pinfunction "7_7") (pintype "passive"))
      (node (ref "J13") (pin "2") (pinfunction "2_2") (pintype "passive"))
    )
    (net (code "41") (name "/J_RST") (class "Default")
      (node (ref "J12") (pin "1") (pinfunction "1_1") (pintype "passive"))
      (node (ref "J13") (pin "9") (pinfunction "9_9") (pintype "passive"))
      (node (ref "K6") (pin "A") (pinfunction "A_A") (pintype "passive"))
    )
    (net (code "42") (name "/KEY1") (class "Default")
      (node (ref "K1") (pin "B") (pinfunction "B_B") (pintype "passive"))
      (node (ref "R26") (pin "1") (pinfunction "1_1") (pintype "passive"))
      (node (ref "U5") (pin "45") (pinfunction "E10_45") (pintype "passive"))
    )
    (net (code "43") (name "/KEY2") (class "Default")
      (node (ref "K2") (pin "B") (pinfunction "B_B") (pintype "passive"))
      (node (ref "R27") (pin "1") (pinfunction "1_1") (pintype "passive"))
      (node (ref "U5") (pin "43") (pinfunction "E9_43") (pintype "passive"))
    )
    (net (code "44") (name "/KEY3") (class "Default")
      (node (ref "K3") (pin "B") (pinfunction "B_B") (pintype "passive"))
      (node (ref "R28") (pin "1") (pinfunction "1_1") (pintype "passive"))
      (node (ref "U5") (pin "46") (pinfunction "E12_46") (pintype "passive"))
    )
    (net (code "45") (name "/KEY4") (class "Default")
      (node (ref "K4") (pin "B") (pinfunction "B_B") (pintype "passive"))
      (node (ref "R29") (pin "1") (pinfunction "1_1") (pintype "passive"))
      (node (ref "U5") (pin "44") (pinfunction "E11_44") (pintype "passive"))
    )
    (net (code "46") (name "/KEY5") (class "Default")
      (node (ref "K5") (pin "B") (pinfunction "B_B") (pintype "passive"))
      (node (ref "R25") (pin "1") (pinfunction "1_1") (pintype "passive"))
      (node (ref "U5") (pin "41") (pinfunction "E8_41") (pintype "passive"))
    )
    (net (code "47") (name "/LC1") (class "Default")
      (node (ref "J9") (pin "1") (pinfunction "1_1") (pintype "passive"))
      (node (ref "U3") (pin "5") (pinfunction "+IN2_5") (pintype "passive"))
    )
    (net (code "48") (name "/LC2") (class "Default")
      (node (ref "J9") (pin "3") (pinfunction "3_3") (pintype "passive"))
      (node (ref "U3") (pin "3") (pinfunction "+IN1_3") (pintype "passive"))
    )
    (net (code "49") (name "/LC3") (class "Default")
      (node (ref "J10") (pin "1") (pinfunction "1_1") (pintype "passive"))
      (node (ref "U1") (pin "5") (pinfunction "+IN2_5") (pintype "passive"))
    )
    (net (code "50") (name "/LC4") (class "Default")
      (node (ref "J10") (pin "3") (pinfunction "3_3") (pintype "passive"))
      (node (ref "U1") (pin "3") (pinfunction "+IN1_3") (pintype "passive"))
    )
    (net (code "51") (name "/LC5") (class "Default")
      (node (ref "J11") (pin "1") (pinfunction "1_1") (pintype "passive"))
      (node (ref "U2") (pin "5") (pinfunction "+IN2_5") (pintype "passive"))
    )
    (net (code "52") (name "/LC6") (class "Default")
      (node (ref "J11") (pin "3") (pinfunction "3_3") (pintype "passive"))
      (node (ref "U2") (pin "3") (pinfunction "+IN1_3") (pintype "passive"))
    )
    (net (code "53") (name "/LCD_CS") (class "Default")
      (node (ref "J6") (pin "9") (pinfunction "9_9") (pintype "passive"))
      (node (ref "U5") (pin "7") (pinfunction "C11_7") (pintype "passive"))
    )
    (net (code "54") (name "/LCD_D0") (class "Default")
      (node (ref "J6") (pin "11") (pinfunction "11_11") (pintype "passive"))
      (node (ref "U5") (pin "85") (pinfunction "C0_85") (pintype "passive"))
    )
    (net (code "55") (name "/LCD_D1") (class "Default")
      (node (ref "J6") (pin "12") (pinfunction "12_12") (pintype "passive"))
      (node (ref "U5") (pin "84") (pinfunction "C1_84") (pintype "passive"))
    )
    (net (code "56") (name "/LCD_D2") (class "Default")
      (node (ref "J6") (pin "13") (pinfunction "13_13") (pintype "passive"))
      (node (ref "U5") (pin "82") (pinfunction "C2_82") (pintype "passive"))
    )
    (net (code "57") (name "/LCD_D3") (class "Default")
      (node (ref "J6") (pin "14") (pinfunction "14_14") (pintype "passive"))
      (node (ref "U5") (pin "83") (pinfunction "C3_83") (pintype "passive"))
    )
    (net (code "58") (name "/LCD_D4") (class "Default")
      (node (ref "J6") (pin "15") (pinfunction "15_15") (pintype "passive"))
      (node (ref "U5") (pin "81") (pinfunction "C4_81") (pintype "passive"))
    )
    (net (code "59") (name "/LCD_D5") (class "Default")
      (node (ref "J6") (pin "16") (pinfunction "16_16") (pintype "passive"))
      (node (ref "U5") (pin "1") (pinfunction "C5_1") (pintype "passive"))
    )
    (net (code "60") (name "/LCD_D6") (class "Default")
      (node (ref "J6") (pin "17") (pinfunction "17_17") (pintype "passive"))
      (node (ref "U5") (pin "2") (pinfunction "C6_2") (pintype "passive"))
    )
    (net (code "61") (name "/LCD_D7") (class "Default")
      (node (ref "J6") (pin "18") (pinfunction "18_18") (pintype "passive"))
      (node (ref "U5") (pin "3") (pinfunction "C7_3") (pintype "passive"))
    )
    (net (code "62") (name "/LCD_RD") (class "Default")
      (node (ref "J6") (pin "2") (pinfunction "2_2") (pintype "passive"))
      (node (ref "U5") (pin "6") (pinfunction "C10_6") (pintype "passive"))
    )
    (net (code "63") (name "/LCD_RS") (class "Default")
      (node (ref "J6") (pin "5") (pinfunction "5_5") (pintype "passive"))
      (node (ref "U5") (pin "8") (pinfunction "C12_8") (pintype "passive"))
    )
    (net (code "64") (name "/LCD_RST") (class "Default")
      (node (ref "J6") (pin "8") (pinfunction "8_8") (pintype "passive"))
      (node (ref "U5") (pin "9") (pinfunction "C13_9") (pintype "passive"))
    )
    (net (code "65") (name "/LCD_WR") (class "Default")
      (node (ref "J6") (pin "7") (pinfunction "7_7") (pintype "passive"))
      (node (ref "U5") (pin "5") (pinfunction "C9_5") (pintype "passive"))
    )
    (net (code "66") (name "/PWM_Motor1+") (class "Default")
      (node (ref "J2") (pin "5") (pinfunction "5_5") (pintype "passive"))
      (node (ref "JP1") (pin "5") (pinfunction "5_5") (pintype "passive"))
      (node (ref "U5") (pin "26") (pinfunction "D7_26") (pintype "passive"))
    )
    (net (code "67") (name "/PWM_Motor1-") (class "Default")
      (node (ref "J2") (pin "4") (pinfunction "4_4") (pintype "passive"))
      (node (ref "JP1") (pin "4") (pinfunction "4_4") (pintype "passive"))
      (node (ref "U5") (pin "22") (pinfunction "D6_22") (pintype "passive"))
    )
    (net (code "68") (name "/PWM_Motor2+") (class "Default")
      (node (ref "J2") (pin "3") (pinfunction "3_3") (pintype "passive"))
      (node (ref "JP1") (pin "3") (pinfunction "3_3") (pintype "passive"))
      (node (ref "U5") (pin "21") (pinfunction "D5_21") (pintype "passive"))
    )
    (net (code "69") (name "/PWM_Motor2-") (class "Default")
      (node (ref "J2") (pin "2") (pinfunction "2_2") (pintype "passive"))
      (node (ref "JP1") (pin "2") (pinfunction "2_2") (pintype "passive"))
      (node (ref "U5") (pin "20") (pinfunction "D4_20") (pintype "passive"))
    )
    (net (code "70") (name "/SW1") (class "Default")
      (node (ref "RN1") (pin "4") (pinfunction "4_4") (pintype "passive"))
      (node (ref "SW2") (pin "1") (pinfunction "1_1") (pintype "passive"))
      (node (ref "U5") (pin "33") (pinfunction "D15_33") (pintype "passive"))
    )
    (net (code "71") (name "/SW2") (class "Default")
      (node (ref "RN1") (pin "3") (pinfunction "3_3") (pintype "passive"))
      (node (ref "SW2") (pin "2") (pinfunction "2_2") (pintype "passive"))
      (node (ref "U5") (pin "31") (pinfunction "D13_31") (pintype "passive"))
    )
    (net (code "72") (name "/SW3") (class "Default")
      (node (ref "RN1") (pin "2") (pinfunction "2_2") (pintype "passive"))
      (node (ref "SW2") (pin "3") (pinfunction "3_3") (pintype "passive"))
      (node (ref "U5") (pin "29") (pinfunction "D11_29") (pintype "passive"))
    )
    (net (code "73") (name "/SW4") (class "Default")
      (node (ref "RN1") (pin "1") (pinfunction "1_1") (pintype "passive"))
      (node (ref "SW2") (pin "4") (pinfunction "4_4") (pintype "passive"))
      (node (ref "U5") (pin "27") (pinfunction "D10_27") (pintype "passive"))
    )
    (net (code "74") (name "/TOF_RXD") (class "Default")
      (node (ref "J7") (pin "3") (pinfunction "3_3") (pintype "passive"))
      (node (ref "U5") (pin "38") (pinfunction "E4_38") (pintype "passive"))
    )
    (net (code "75") (name "/TOF_TXD") (class "Default")
      (node (ref "J7") (pin "4") (pinfunction "4_4") (pintype "passive"))
      (node (ref "U5") (pin "39") (pinfunction "E5_39") (pintype "passive"))
    )
    (net (code "76") (name "/VEE") (class "Default")
      (node (ref "JP3") (pin "2") (pinfunction "2_2") (pintype "passive"))
      (node (ref "P1") (pin "2") (pinfunction "2_2") (pintype "passive"))
      (node (ref "Q1") (pin "4") (pinfunction "D_4") (pintype "passive"))
    )
    (net (code "77") (name "7.2V") (class "Default")
      (node (ref "C12") (pin "1") (pinfunction "1_1") (pintype "passive"))
      (node (ref "C13") (pin "1") (pinfunction "1_1") (pintype "passive"))
      (node (ref "D11") (pin "1") (pinfunction "A_1") (pintype "passive"))
      (node (ref "F1") (pin "1") (pinfunction "1_1") (pintype "passive"))
      (node (ref "R30") (pin "2") (pinfunction "2_2") (pintype "passive"))
      (node (ref "R31") (pin "1") (pinfunction "1_1") (pintype "passive"))
      (node (ref "U6") (pin "1") (pinfunction "VIN_1") (pintype "passive"))
    )
    (net (code "78") (name "AGND") (class "Default")
      (node (ref "C1") (pin "2") (pinfunction "2_2") (pintype "passive"))
      (node (ref "C2") (pin "2") (pinfunction "2_2") (pintype "passive"))
      (node (ref "C3") (pin "2") (pinfunction "2_2") (pintype "passive"))
      (node (ref "C4") (pin "2") (pinfunction "2_2") (pintype "passive"))
      (node (ref "C5") (pin "2") (pinfunction "2_2") (pintype "passive"))
      (node (ref "C6") (pin "2") (pinfunction "2_2") (pintype "passive"))
      (node (ref "C7") (pin "2") (pinfunction "2_2") (pintype "passive"))
      (node (ref "C8") (pin "2") (pinfunction "2_2") (pintype "passive"))
      (node (ref "C9") (pin "2") (pinfunction "2_2") (pintype "passive"))
      (node (ref "D1") (pin "2") (pinfunction "A_2") (pintype "passive"))
      (node (ref "D2") (pin "2") (pinfunction "A_2") (pintype "passive"))
      (node (ref "D5") (pin "2") (pinfunction "A_2") (pintype "passive"))
      (node (ref "D6") (pin "2") (pinfunction "A_2") (pintype "passive"))
      (node (ref "D7") (pin "2") (pinfunction "A_2") (pintype "passive"))
      (node (ref "D8") (pin "2") (pinfunction "A_2") (pintype "passive"))
      (node (ref "J10") (pin "2") (pinfunction "2_2") (pintype "passive"))
      (node (ref "J11") (pin "2") (pinfunction "2_2") (pintype "passive"))
      (node (ref "J9") (pin "2") (pinfunction "2_2") (pintype "passive"))
      (node (ref "R11") (pin "1") (pinfunction "1_1") (pintype "passive"))
      (node (ref "R12") (pin "1") (pinfunction "1_1") (pintype "passive"))
      (node (ref "R14") (pin "2") (pinfunction "2_2") (pintype "passive"))
      (node (ref "R15") (pin "2") (pinfunction "2_2") (pintype "passive"))
      (node (ref "R22") (pin "1") (pinfunction "1_1") (pintype "passive"))
      (node (ref "R23") (pin "2") (pinfunction "2_2") (pintype "passive"))
      (node (ref "R24") (pin "1") (pinfunction "1_1") (pintype "passive"))
      (node (ref "U1") (pin "4") (pinfunction "GND_4") (pintype "passive"))
      (node (ref "U2") (pin "4") (pinfunction "GND_4") (pintype "passive"))
      (node (ref "U3") (pin "4") (pinfunction "GND_4") (pintype "passive"))
    )
    (net (code "79") (name "GND") (class "Default")
      (node (ref "C10") (pin "2") (pinfunction "2_2") (pintype "passive"))
      (node (ref "C11") (pin "2") (pinfunction "2_2") (pintype "passive"))
      (node (ref "C12") (pin "2") (pinfunction "2_2") (pintype "passive"))
      (node (ref "C13") (pin "2") (pinfunction "2_2") (pintype "passive"))
      (node (ref "C14") (pin "2") (pinfunction "2_2") (pintype "passive"))
      (node (ref "C15") (pin "1") (pinfunction "1_1") (pintype "passive"))
      (node (ref "D10") (pin "1") (pinfunction "A_1") (pintype "passive"))
      (node (ref "D3") (pin "2") (pinfunction "A_2") (pintype "passive"))
      (node (ref "D4") (pin "2") (pinfunction "A_2") (pintype "passive"))
      (node (ref "D9") (pin "C") (pinfunction "C_C") (pintype "passive"))
      (node (ref "FM1") (pin "2") (pinfunction "－_2") (pintype "passive"))
      (node (ref "J1") (pin "2") (pinfunction "2_2") (pintype "passive"))
      (node (ref "J12") (pin "10") (pinfunction "10_10") (pintype "passive"))
      (node (ref "J12") (pin "8") (pinfunction "8_8") (pintype "passive"))
      (node (ref "J13") (pin "6") (pinfunction "6_6") (pintype "passive"))
      (node (ref "J2") (pin "1") (pinfunction "1_1") (pintype "passive"))
      (node (ref "J3") (pin "1") (pinfunction "1_1") (pintype "passive"))
      (node (ref "J4") (pin "1") (pinfunction "1_1") (pintype "passive"))
      (node (ref "J5") (pin "2") (pinfunction "2_2") (pintype "passive"))
      (node (ref "J6") (pin "1") (pinfunction "1_1") (pintype "passive"))
      (node (ref "J7") (pin "1") (pinfunction "1_1") (pintype "passive"))
      (node (ref "J8") (pin "11") (pinfunction "11_11") (pintype "passive"))
      (node (ref "JP1") (pin "1") (pinfunction "1_1") (pintype "passive"))
      (node (ref "JP2") (pin "21") (pinfunction "21_21") (pintype "passive"))
      (node (ref "K1") (pin "A") (pinfunction "A_A") (pintype "passive"))
      (node (ref "K2") (pin "A") (pinfunction "A_A") (pintype "passive"))
      (node (ref "K3") (pin "A") (pinfunction "A_A") (pintype "passive"))
      (node (ref "K4") (pin "A") (pinfunction "A_A") (pintype "passive"))
      (node (ref "K5") (pin "A") (pinfunction "A_A") (pintype "passive"))
      (node (ref "K6") (pin "B") (pinfunction "B_B") (pintype "passive"))
      (node (ref "Q1") (pin "3") (pinfunction "S_3") (pintype "passive"))
      (node (ref "R24") (pin "2") (pinfunction "2_2") (pintype "passive"))
      (node (ref "R33") (pin "2") (pinfunction "2_2") (pintype "passive"))
      (node (ref "R38") (pin "1") (pinfunction "1_1") (pintype "passive"))
      (node (ref "SW2") (pin "5") (pinfunction "5_5") (pintype "passive"))
      (node (ref "SW2") (pin "6") (pinfunction "6_6") (pintype "passive"))
      (node (ref "SW2") (pin "7") (pinfunction "7_7") (pintype "passive"))
      (node (ref "SW2") (pin "8") (pinfunction "8_8") (pintype "passive"))
      (node (ref "U4") (pin "1") (pinfunction "GND_1") (pintype "passive"))
      (node (ref "U5") (pin "23") (pinfunction "GND_23") (pintype "passive"))
      (node (ref "U6") (pin "3") (pinfunction "GND_3") (pintype "passive"))
      (node (ref "U6") (pin "5") (pinfunction "ON#/OFF_5") (pintype "passive"))
      (node (ref "U6") (pin "6") (pinfunction "GND_6") (pintype "passive"))
      (node (ref "U7") (pin "1") (pinfunction "GND_1") (pintype "passive"))
      (node (ref "U7") (pin "2") (pinfunction "EN_2") (pintype "passive"))
    )
    (net (code "80") (name "Net-(C16-Pad2)") (class "Default")
      (node (ref "C16") (pin "2") (pinfunction "2_2") (pintype "passive"))
      (node (ref "R38") (pin "2") (pinfunction "2_2") (pintype "passive"))
    )
    (net (code "81") (name "Net-(D9-PadA)") (class "Default")
      (node (ref "D9") (pin "A") (pinfunction "A_A") (pintype "passive"))
      (node (ref "R30") (pin "1") (pinfunction "1_1") (pintype "passive"))
    )
    (net (code "82") (name "Net-(D10-C)") (class "Default")
      (node (ref "D10") (pin "2") (pinfunction "C_2") (pintype "passive"))
      (node (ref "L1") (pin "2") (pinfunction "2_2") (pintype "passive"))
      (node (ref "U6") (pin "2") (pinfunction "OUTPUT_2") (pintype "passive"))
    )
    (net (code "83") (name "Net-(D11-C)") (class "Default")
      (node (ref "C15") (pin "2") (pinfunction "2_2") (pintype "passive"))
      (node (ref "D11") (pin "2") (pinfunction "C_2") (pintype "passive"))
      (node (ref "U7") (pin "3") (pinfunction "IN/2_3") (pintype "passive"))
      (node (ref "U7") (pin "4") (pinfunction "IN_4") (pintype "passive"))
    )
    (net (code "84") (name "Net-(FM1-+)") (class "Default")
      (node (ref "FM1") (pin "1") (pinfunction "+_1") (pintype "passive"))
      (node (ref "Q2") (pin "3") (pinfunction "C_3") (pintype "passive"))
    )
    (net (code "85") (name "Net-(J5-Pad3)") (class "Default")
      (node (ref "J5") (pin "3") (pinfunction "3_3") (pintype "passive"))
      (node (ref "R16") (pin "2") (pinfunction "2_2") (pintype "passive"))
    )
    (net (code "86") (name "Net-(J5-Pad4)") (class "Default")
      (node (ref "J5") (pin "4") (pinfunction "4_4") (pintype "passive"))
      (node (ref "R13") (pin "2") (pinfunction "2_2") (pintype "passive"))
    )
    (net (code "87") (name "Net-(J6-Pad10)") (class "Default")
      (node (ref "J6") (pin "10") (pinfunction "10_10") (pintype "passive"))
      (node (ref "R17") (pin "1") (pinfunction "1_1") (pintype "passive"))
    )
    (net (code "88") (name "Net-(Q2-B)") (class "Default")
      (node (ref "Q2") (pin "2") (pinfunction "B_2") (pintype "passive"))
      (node (ref "R34") (pin "2") (pinfunction "2_2") (pintype "passive"))
      (node (ref "R35") (pin "2") (pinfunction "2_2") (pintype "passive"))
    )
    (net (code "89") (name "Net-(R31-Pad2)") (class "Default")
      (node (ref "R31") (pin "2") (pinfunction "2_2") (pintype "passive"))
      (node (ref "R32") (pin "1") (pinfunction "1_1") (pintype "passive"))
      (node (ref "R33") (pin "1") (pinfunction "1_1") (pintype "passive"))
    )
    (net (code "90") (name "Net-(SW1-C)") (class "Default")
      (node (ref "F1") (pin "2") (pinfunction "2_2") (pintype "passive"))
      (node (ref "SW1") (pin "2") (pinfunction "C_2") (pintype "passive"))
    )
    (net (code "91") (name "Net-(U1--IN1)") (class "Default")
      (node (ref "R14") (pin "1") (pinfunction "1_1") (pintype "passive"))
      (node (ref "R7") (pin "3") (pinfunction "3_3") (pintype "passive"))
      (node (ref "U1") (pin "2") (pinfunction "-IN1_2") (pintype "passive"))
    )
    (net (code "92") (name "Net-(U1--IN2)") (class "Default")
      (node (ref "R11") (pin "2") (pinfunction "2_2") (pintype "passive"))
      (node (ref "R9") (pin "1") (pinfunction "1_1") (pintype "passive"))
      (node (ref "U1") (pin "6") (pinfunction "-IN2_6") (pintype "passive"))
    )
    (net (code "93") (name "Net-(U1-OUT1)") (class "Default")
      (node (ref "R1") (pin "2") (pinfunction "2_2") (pintype "passive"))
      (node (ref "R7") (pin "2") (pinfunction "2_2") (pintype "passive"))
      (node (ref "U1") (pin "1") (pinfunction "OUT1_1") (pintype "passive"))
    )
    (net (code "94") (name "Net-(U1-OUT2)") (class "Default")
      (node (ref "R5") (pin "2") (pinfunction "2_2") (pintype "passive"))
      (node (ref "R9") (pin "2") (pinfunction "2_2") (pintype "passive"))
      (node (ref "U1") (pin "7") (pinfunction "OUT2_7") (pintype "passive"))
    )
    (net (code "95") (name "Net-(U2--IN1)") (class "Default")
      (node (ref "R15") (pin "1") (pinfunction "1_1") (pintype "passive"))
      (node (ref "R8") (pin "3") (pinfunction "3_3") (pintype "passive"))
      (node (ref "U2") (pin "2") (pinfunction "-IN1_2") (pintype "passive"))
    )
    (net (code "96") (name "Net-(U2--IN2)") (class "Default")
      (node (ref "R10") (pin "1") (pinfunction "1_1") (pintype "passive"))
      (node (ref "R12") (pin "2") (pinfunction "2_2") (pintype "passive"))
      (node (ref "U2") (pin "6") (pinfunction "-IN2_6") (pintype "passive"))
    )
    (net (code "97") (name "Net-(U2-OUT1)") (class "Default")
      (node (ref "R2") (pin "2") (pinfunction "2_2") (pintype "passive"))
      (node (ref "R8") (pin "2") (pinfunction "2_2") (pintype "passive"))
      (node (ref "U2") (pin "1") (pinfunction "OUT1_1") (pintype "passive"))
    )
    (net (code "98") (name "Net-(U2-OUT2)") (class "Default")
      (node (ref "R10") (pin "2") (pinfunction "2_2") (pintype "passive"))
      (node (ref "R6") (pin "2") (pinfunction "2_2") (pintype "passive"))
      (node (ref "U2") (pin "7") (pinfunction "OUT2_7") (pintype "passive"))
    )
    (net (code "99") (name "Net-(U3--IN1)") (class "Default")
      (node (ref "R20") (pin "3") (pinfunction "3_3") (pintype "passive"))
      (node (ref "R23") (pin "1") (pinfunction "1_1") (pintype "passive"))
      (node (ref "U3") (pin "2") (pinfunction "-IN1_2") (pintype "passive"))
    )
    (net (code "100") (name "Net-(U3--IN2)") (class "Default")
      (node (ref "R21") (pin "1") (pinfunction "1_1") (pintype "passive"))
      (node (ref "R22") (pin "2") (pinfunction "2_2") (pintype "passive"))
      (node (ref "U3") (pin "6") (pinfunction "-IN2_6") (pintype "passive"))
    )
    (net (code "101") (name "Net-(U3-OUT1)") (class "Default")
      (node (ref "R18") (pin "2") (pinfunction "2_2") (pintype "passive"))
      (node (ref "R20") (pin "2") (pinfunction "2_2") (pintype "passive"))
      (node (ref "U3") (pin "1") (pinfunction "OUT1_1") (pintype "passive"))
    )
    (net (code "102") (name "Net-(U3-OUT2)") (class "Default")
      (node (ref "R19") (pin "2") (pinfunction "2_2") (pintype "passive"))
      (node (ref "R21") (pin "2") (pinfunction "2_2") (pintype "passive"))
      (node (ref "U3") (pin "7") (pinfunction "OUT2_7") (pintype "passive"))
    )
    (net (code "103") (name "Net-(U6-FB)") (class "Default")
      (node (ref "C14") (pin "1") (pinfunction "1_1") (pintype "passive"))
      (node (ref "F2") (pin "1") (pinfunction "1_1") (pintype "passive"))
      (node (ref "L1") (pin "1") (pinfunction "1_1") (pintype "passive"))
      (node (ref "U6") (pin "4") (pinfunction "FB_4") (pintype "passive"))
    )
    (net (code "104") (name "Net-(U7-OUT)") (class "Default")
      (node (ref "C16") (pin "1") (pinfunction "1_1") (pintype "passive"))
      (node (ref "R36") (pin "1") (pinfunction "1_1") (pintype "passive"))
      (node (ref "R37") (pin "2") (pinfunction "2_2") (pintype "passive"))
      (node (ref "U7") (pin "5") (pinfunction "OUT/2_5") (pintype "passive"))
      (node (ref "U7") (pin "6") (pinfunction "OUT_6") (pintype "passive"))
      (node (ref "U7") (pin "7") (pinfunction "SENSEFB_7") (pintype "passive"))
    )
    (net (code "105") (name "Net-(U7-RESET)") (class "Default")
      (node (ref "R37") (pin "1") (pinfunction "1_1") (pintype "passive"))
      (node (ref "U7") (pin "8") (pinfunction "RESET_8") (pintype "passive"))
    )
    (net (code "106") (name "VCC5V_MCU") (class "Default")
      (node (ref "R36") (pin "2") (pinfunction "2_2") (pintype "passive"))
      (node (ref "U5") (pin "24") (pinfunction "5V_24") (pintype "passive"))
    )
    (net (code "107") (name "VCC_3.3V") (class "Default")
      (node (ref "C11") (pin "1") (pinfunction "1_1") (pintype "passive"))
      (node (ref "J1") (pin "1") (pinfunction "1_1") (pintype "passive"))
      (node (ref "J7") (pin "2") (pinfunction "2_2") (pintype "passive"))
      (node (ref "J8") (pin "20") (pinfunction "20_20") (pintype "passive"))
      (node (ref "JP2") (pin "22") (pinfunction "22_22") (pintype "passive"))
      (node (ref "Q2") (pin "1") (pinfunction "E_1") (pintype "passive"))
      (node (ref "R17") (pin "2") (pinfunction "2_2") (pintype "passive"))
      (node (ref "R25") (pin "2") (pinfunction "2_2") (pintype "passive"))
      (node (ref "R26") (pin "2") (pinfunction "2_2") (pintype "passive"))
      (node (ref "R27") (pin "2") (pinfunction "2_2") (pintype "passive"))
      (node (ref "R28") (pin "2") (pinfunction "2_2") (pintype "passive"))
      (node (ref "R29") (pin "2") (pinfunction "2_2") (pintype "passive"))
      (node (ref "R34") (pin "1") (pinfunction "1_1") (pintype "passive"))
      (node (ref "RN1") (pin "5") (pinfunction "5_5") (pintype "passive"))
      (node (ref "RN1") (pin "6") (pinfunction "6_6") (pintype "passive"))
      (node (ref "RN1") (pin "7") (pinfunction "7_7") (pintype "passive"))
      (node (ref "RN1") (pin "8") (pinfunction "8_8") (pintype "passive"))
      (node (ref "U4") (pin "2") (pinfunction "Out_2") (pintype "passive"))
      (node (ref "U4") (pin "4") (pinfunction "TAB_4") (pintype "passive"))
    )
    (net (code "108") (name "VCC_5V") (class "Default")
      (node (ref "C10") (pin "1") (pinfunction "1_1") (pintype "passive"))
      (node (ref "C3") (pin "1") (pinfunction "1_1") (pintype "passive"))
      (node (ref "C4") (pin "1") (pinfunction "1_1") (pintype "passive"))
      (node (ref "C8") (pin "1") (pinfunction "1_1") (pintype "passive"))
      (node (ref "F2") (pin "2") (pinfunction "2_2") (pintype "passive"))
      (node (ref "J3") (pin "6") (pinfunction "6_6") (pintype "passive"))
      (node (ref "J4") (pin "6") (pinfunction "6_6") (pintype "passive"))
      (node (ref "J5") (pin "1") (pinfunction "1_1") (pintype "passive"))
      (node (ref "U1") (pin "8") (pinfunction "VCC+_8") (pintype "passive"))
      (node (ref "U2") (pin "8") (pinfunction "VCC+_8") (pintype "passive"))
      (node (ref "U3") (pin "8") (pinfunction "VCC+_8") (pintype "passive"))
      (node (ref "U4") (pin "3") (pinfunction "In_3") (pintype "passive"))
    )
    (net (code "109") (name "unconnected-(J2-Pad6)") (class "Default")
      (node (ref "J2") (pin "6") (pinfunction "6_6") (pintype "passive"))
    )
    (net (code "110") (name "unconnected-(J3-Pad3)") (class "Default")
      (node (ref "J3") (pin "3") (pinfunction "3_3") (pintype "passive"))
    )
    (net (code "111") (name "unconnected-(J3-Pad4)") (class "Default")
      (node (ref "J3") (pin "4") (pinfunction "4_4") (pintype "passive"))
    )
    (net (code "112") (name "unconnected-(J4-Pad3)") (class "Default")
      (node (ref "J4") (pin "3") (pinfunction "3_3") (pintype "passive"))
    )
    (net (code "113") (name "unconnected-(J4-Pad4)") (class "Default")
      (node (ref "J4") (pin "4") (pinfunction "4_4") (pintype "passive"))
    )
    (net (code "114") (name "unconnected-(J6-Pad3)") (class "Default")
      (node (ref "J6") (pin "3") (pinfunction "3_3") (pintype "passive"))
    )
    (net (code "115") (name "unconnected-(J6-Pad4)") (class "Default")
      (node (ref "J6") (pin "4") (pinfunction "4_4") (pintype "passive"))
    )
    (net (code "116") (name "unconnected-(J6-Pad6)") (class "Default")
      (node (ref "J6") (pin "6") (pinfunction "6_6") (pintype "passive"))
    )
    (net (code "117") (name "unconnected-(J6-Pad19)") (class "Default")
      (node (ref "J6") (pin "19") (pinfunction "19_19") (pintype "passive"))
    )
    (net (code "118") (name "unconnected-(J6-Pad20)") (class "Default")
      (node (ref "J6") (pin "20") (pinfunction "20_20") (pintype "passive"))
    )
    (net (code "119") (name "unconnected-(J8-Pad13)") (class "Default")
      (node (ref "J8") (pin "13") (pinfunction "13_13") (pintype "passive"))
    )
    (net (code "120") (name "unconnected-(J8-Pad14)") (class "Default")
      (node (ref "J8") (pin "14") (pinfunction "14_14") (pintype "passive"))
    )
    (net (code "121") (name "unconnected-(J8-Pad16)") (class "Default")
      (node (ref "J8") (pin "16") (pinfunction "16_16") (pintype "passive"))
    )
    (net (code "122") (name "unconnected-(J8-Pad18)") (class "Default")
      (node (ref "J8") (pin "18") (pinfunction "18_18") (pintype "passive"))
    )
    (net (code "123") (name "unconnected-(J8-Pad19)") (class "Default")
      (node (ref "J8") (pin "19") (pinfunction "19_19") (pintype "passive"))
    )
    (net (code "124") (name "unconnected-(J12-Pad9)") (class "Default")
      (node (ref "J12") (pin "9") (pinfunction "9_9") (pintype "passive"))
    )
    (net (code "125") (name "unconnected-(J13-Pad7)") (class "Default")
      (node (ref "J13") (pin "7") (pinfunction "7_7") (pintype "passive"))
    )
    (net (code "126") (name "unconnected-(J13-Pad10)") (class "Default")
      (node (ref "J13") (pin "10") (pinfunction "10_10") (pintype "passive"))
    )
    (net (code "127") (name "unconnected-(JP1-Pad6)") (class "Default")
      (node (ref "JP1") (pin "6") (pinfunction "6_6") (pintype "passive"))
    )
    (net (code "128") (name "unconnected-(JP2-Pad1)") (class "Default")
      (node (ref "JP2") (pin "1") (pinfunction "1_1") (pintype "passive"))
    )
    (net (code "129") (name "unconnected-(JP2-Pad2)") (class "Default")
      (node (ref "JP2") (pin "2") (pinfunction "2_2") (pintype "passive"))
    )
    (net (code "130") (name "unconnected-(JP2-Pad3)") (class "Default")
      (node (ref "JP2") (pin "3") (pinfunction "3_3") (pintype "passive"))
    )
    (net (code "131") (name "unconnected-(JP2-Pad5)") (class "Default")
      (node (ref "JP2") (pin "5") (pinfunction "5_5") (pintype "passive"))
    )
    (net (code "132") (name "unconnected-(JP2-Pad7)") (class "Default")
      (node (ref "JP2") (pin "7") (pinfunction "7_7") (pintype "passive"))
    )
    (net (code "133") (name "unconnected-(JP2-Pad8)") (class "Default")
      (node (ref "JP2") (pin "8") (pinfunction "8_8") (pintype "passive"))
    )
    (net (code "134") (name "unconnected-(JP2-Pad10)") (class "Default")
      (node (ref "JP2") (pin "10") (pinfunction "10_10") (pintype "passive"))
    )
    (net (code "135") (name "unconnected-(JP2-Pad23)") (class "Default")
      (node (ref "JP2") (pin "23") (pinfunction "23_23") (pintype "passive"))
    )
    (net (code "136") (name "unconnected-(JP2-Pad24)") (class "Default")
      (node (ref "JP2") (pin "24") (pinfunction "24_24") (pintype "passive"))
    )
    (net (code "137") (name "unconnected-(R7-Pad1)") (class "Default")
      (node (ref "R7") (pin "1") (pinfunction "1_1") (pintype "passive"))
    )
    (net (code "138") (name "unconnected-(R8-Pad1)") (class "Default")
      (node (ref "R8") (pin "1") (pinfunction "1_1") (pintype "passive"))
    )
    (net (code "139") (name "unconnected-(R9-Pad3)") (class "Default")
      (node (ref "R9") (pin "3") (pinfunction "3_3") (pintype "passive"))
    )
    (net (code "140") (name "unconnected-(R10-Pad3)") (class "Default")
      (node (ref "R10") (pin "3") (pinfunction "3_3") (pintype "passive"))
    )
    (net (code "141") (name "unconnected-(R20-Pad1)") (class "Default")
      (node (ref "R20") (pin "1") (pinfunction "1_1") (pintype "passive"))
    )
    (net (code "142") (name "unconnected-(R21-Pad3)") (class "Default")
      (node (ref "R21") (pin "3") (pinfunction "3_3") (pintype "passive"))
    )
    (net (code "143") (name "unconnected-(SW1-ON-Pad1)") (class "Default")
      (node (ref "SW1") (pin "1") (pinfunction "ON_1") (pintype "passive"))
    )
    (net (code "144") (name "unconnected-(U5A-C8-Pad4)") (class "Default")
      (node (ref "U5") (pin "4") (pinfunction "C8_4") (pintype "passive"))
    )
    (net (code "145") (name "unconnected-(U5A-C14-Pad10)") (class "Default")
      (node (ref "U5") (pin "10") (pinfunction "C14_10") (pintype "passive"))
    )
    (net (code "146") (name "unconnected-(U5A-C16-Pad12)") (class "Default")
      (node (ref "U5") (pin "12") (pinfunction "C16_12") (pintype "passive"))
    )
    (net (code "147") (name "unconnected-(U5A-C17-Pad14)") (class "Default")
      (node (ref "U5") (pin "14") (pinfunction "C17_14") (pintype "passive"))
    )
    (net (code "148") (name "unconnected-(U5A-C18-Pad16)") (class "Default")
      (node (ref "U5") (pin "16") (pinfunction "C18_16") (pintype "passive"))
    )
    (net (code "149") (name "unconnected-(U5A-C19-Pad13)") (class "Default")
      (node (ref "U5") (pin "13") (pinfunction "C19_13") (pintype "passive"))
    )
    (net (code "150") (name "unconnected-(U5A-D0-Pad15)") (class "Default")
      (node (ref "U5") (pin "15") (pinfunction "D0_15") (pintype "passive"))
    )
    (net (code "151") (name "unconnected-(U5A-D1-Pad17)") (class "Default")
      (node (ref "U5") (pin "17") (pinfunction "D1_17") (pintype "passive"))
    )
    (net (code "152") (name "unconnected-(U5B-0DM0-Pad53)") (class "Default")
      (node (ref "U5") (pin "53") (pinfunction "0DM0_53") (pintype "passive"))
    )
    (net (code "153") (name "unconnected-(U5B-0DM1-Pad49)") (class "Default")
      (node (ref "U5") (pin "49") (pinfunction "0DM1_49") (pintype "passive"))
    )
    (net (code "154") (name "unconnected-(U5B-0DP0-Pad54)") (class "Default")
      (node (ref "U5") (pin "54") (pinfunction "0DP0_54") (pintype "passive"))
    )
    (net (code "155") (name "unconnected-(U5B-0DP1-Pad50)") (class "Default")
      (node (ref "U5") (pin "50") (pinfunction "0DP1_50") (pintype "passive"))
    )
    (net (code "156") (name "unconnected-(U5B-1DM1-Pad51)") (class "Default")
      (node (ref "U5") (pin "51") (pinfunction "1DM1_51") (pintype "passive"))
    )
    (net (code "157") (name "unconnected-(U5B-1DP1-Pad52)") (class "Default")
      (node (ref "U5") (pin "52") (pinfunction "1DP1_52") (pintype "passive"))
    )
    (net (code "158") (name "unconnected-(U5B-D12-Pad30)") (class "Default")
      (node (ref "U5") (pin "30") (pinfunction "D12_30") (pintype "passive"))
    )
    (net (code "159") (name "unconnected-(U5B-D14-Pad32)") (class "Default")
      (node (ref "U5") (pin "32") (pinfunction "D14_32") (pintype "passive"))
    )
    (net (code "160") (name "unconnected-(U5B-E0-Pad34)") (class "Default")
      (node (ref "U5") (pin "34") (pinfunction "E0_34") (pintype "passive"))
    )
    (net (code "161") (name "unconnected-(U5B-E2-Pad36)") (class "Default")
      (node (ref "U5") (pin "36") (pinfunction "E2_36") (pintype "passive"))
    )
    (net (code "162") (name "unconnected-(U5B-E6-Pad40)") (class "Default")
      (node (ref "U5") (pin "40") (pinfunction "E6_40") (pintype "passive"))
    )
    (net (code "163") (name "unconnected-(U5B-E7-Pad42)") (class "Default")
      (node (ref "U5") (pin "42") (pinfunction "E7_42") (pintype "passive"))
    )
    (net (code "164") (name "unconnected-(U5B-UDM-Pad47)") (class "Default")
      (node (ref "U5") (pin "47") (pinfunction "UDM_47") (pintype "passive"))
    )
    (net (code "165") (name "unconnected-(U5B-UDP-Pad48)") (class "Default")
      (node (ref "U5") (pin "48") (pinfunction "UDP_48") (pintype "passive"))
    )
    (net (code "166") (name "unconnected-(U5C-0S16-Pad78)") (class "Default")
      (node (ref "U5") (pin "78") (pinfunction "0S16_78") (pintype "passive"))
    )
    (net (code "167") (name "unconnected-(U5C-1S16-Pad77)") (class "Default")
      (node (ref "U5") (pin "77") (pinfunction "1S16_77") (pintype "passive"))
    )
    (net (code "168") (name "unconnected-(U5C-3.3V-Pad80)") (class "Default")
      (node (ref "U5") (pin "80") (pinfunction "3.3V_80") (pintype "passive+no_connect"))
    )
    (net (code "169") (name "unconnected-(U5C-A5-Pad69)") (class "Default")
      (node (ref "U5") (pin "69") (pinfunction "A5_69") (pintype "passive"))
    )
    (net (code "170") (name "unconnected-(U5C-A6-Pad68)") (class "Default")
      (node (ref "U5") (pin "68") (pinfunction "A6_68") (pintype "passive"))
    )
    (net (code "171") (name "unconnected-(U5C-A12-Pad62)") (class "Default")
      (node (ref "U5") (pin "62") (pinfunction "A12_62") (pintype "passive"))
    )
    (net (code "172") (name "unconnected-(U5C-A13-Pad61)") (class "Default")
      (node (ref "U5") (pin "61") (pinfunction "A13_61") (pintype "passive"))
    )
    (net (code "173") (name "unconnected-(U5C-A14-Pad60)") (class "Default")
      (node (ref "U5") (pin "60") (pinfunction "A14_60") (pintype "passive"))
    )
    (net (code "174") (name "unconnected-(U5C-A15-Pad59)") (class "Default")
      (node (ref "U5") (pin "59") (pinfunction "A15_59") (pintype "passive"))
    )
    (net (code "175") (name "unconnected-(U5C-A16-Pad58)") (class "Default")
      (node (ref "U5") (pin "58") (pinfunction "A16_58") (pintype "passive"))
    )
    (net (code "176") (name "unconnected-(U5C-DA0-Pad76)") (class "Default")
      (node (ref "U5") (pin "76") (pinfunction "DA0_76") (pintype "passive"))
    )
    (net (code "177") (name "unconnected-(U5C-DA1-Pad75)") (class "Default")
      (node (ref "U5") (pin "75") (pinfunction "DA1_75") (pintype "passive"))
    )
    (net (code "178") (name "unconnected-(U5C-E26-Pad72)") (class "Default")
      (node (ref "U5") (pin "72") (pinfunction "E26_72") (pintype "passive+no_connect"))
    )
    (net (code "179") (name "unconnected-(U5C-E27-Pad71)") (class "Default")
      (node (ref "U5") (pin "71") (pinfunction "E27_71") (pintype "passive+no_connect"))
    )
    (net (code "180") (name "unconnected-(U5C-E28-Pad70)") (class "Default")
      (node (ref "U5") (pin "70") (pinfunction "E28_70") (pintype "passive"))
    )
    (net (code "181") (name "unconnected-(U5C-REF-Pad79)") (class "Default")
      (node (ref "U5") (pin "79") (pinfunction "REF_79") (pintype "passive+no_connect"))
    )
    (net (code "182") (name "unconnected-(U5D-A19-Pad111)") (class "Default")
      (node (ref "U5") (pin "111") (pinfunction "A19_111") (pintype "passive"))
    )
    (net (code "183") (name "unconnected-(U5D-A24-Pad109)") (class "Default")
      (node (ref "U5") (pin "109") (pinfunction "A24_109") (pintype "passive"))
    )
    (net (code "184") (name "unconnected-(U5D-B8-Pad97)") (class "Default")
      (node (ref "U5") (pin "97") (pinfunction "B8_97") (pintype "passive"))
    )
    (net (code "185") (name "unconnected-(U5D-B9-Pad96)") (class "Default")
      (node (ref "U5") (pin "96") (pinfunction "B9_96") (pintype "passive+no_connect"))
    )
    (net (code "186") (name "unconnected-(U5D-B11-Pad95)") (class "Default")
      (node (ref "U5") (pin "95") (pinfunction "B11_95") (pintype "passive+no_connect"))
    )
    (net (code "187") (name "unconnected-(U5D-B16-Pad92)") (class "Default")
      (node (ref "U5") (pin "92") (pinfunction "B16_92") (pintype "passive"))
    )
    (net (code "188") (name "unconnected-(U5D-B17-Pad93)") (class "Default")
      (node (ref "U5") (pin "93") (pinfunction "B17_93") (pintype "passive"))
    )
    (net (code "189") (name "unconnected-(U5D-B18-Pad90)") (class "Default")
      (node (ref "U5") (pin "90") (pinfunction "B18_90") (pintype "passive"))
    )
    (net (code "190") (name "unconnected-(U5D-B19-Pad91)") (class "Default")
      (node (ref "U5") (pin "91") (pinfunction "B19_91") (pintype "passive"))
    )
    (net (code "191") (name "unconnected-(U5D-B20-Pad88)") (class "Default")
      (node (ref "U5") (pin "88") (pinfunction "B20_88") (pintype "passive"))
    )
    (net (code "192") (name "unconnected-(U5D-B21-Pad89)") (class "Default")
      (node (ref "U5") (pin "89") (pinfunction "B21_89") (pintype "passive"))
    )
    (net (code "193") (name "unconnected-(U5D-B22-Pad86)") (class "Default")
      (node (ref "U5") (pin "86") (pinfunction "B22_86") (pintype "passive"))
    )
    (net (code "194") (name "unconnected-(U5D-B23-Pad87)") (class "Default")
      (node (ref "U5") (pin "87") (pinfunction "B23_87") (pintype "passive"))
    )
  )
)
